# ReducedSolidWorksModel.net
KiCad netlist of a schematic drawn in EAGLE
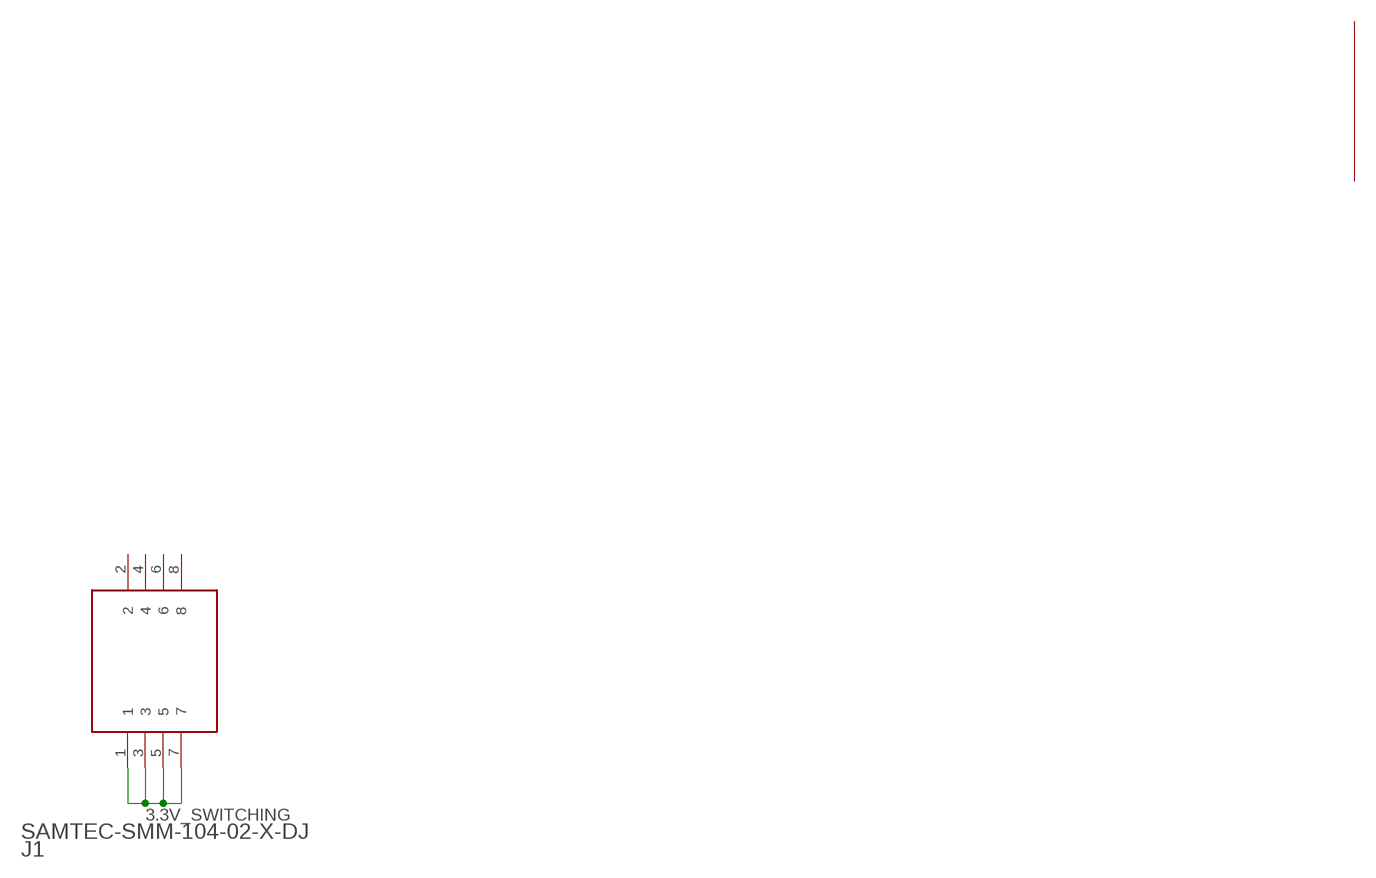
[diagram p0: schematic, sheet 3]
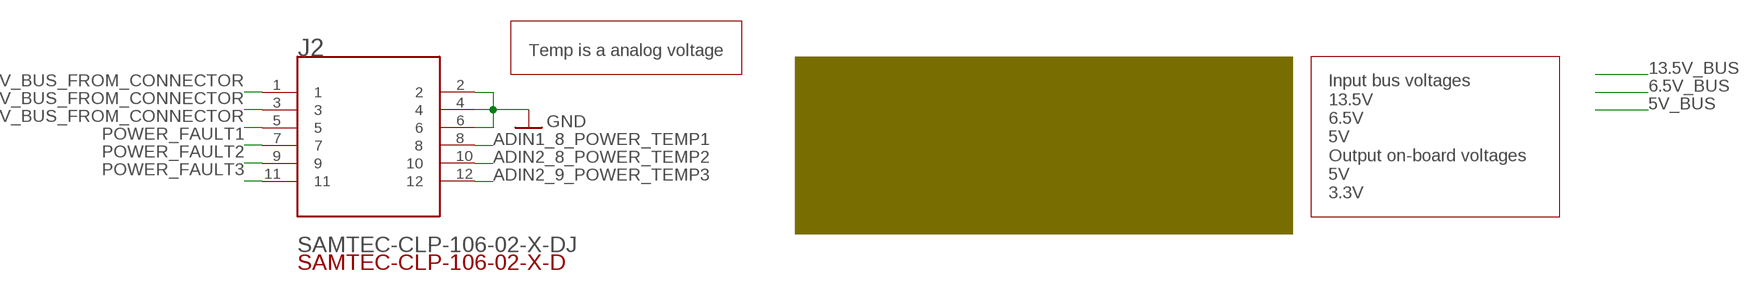
[diagram p1: schematic, sheet 4]
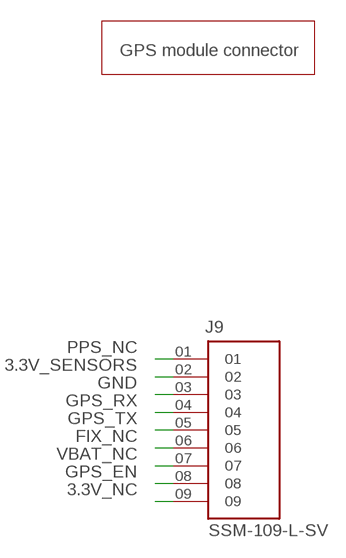
[diagram p2: schematic, sheet 7]
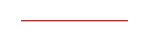
[diagram p3: schematic, sheet 10]
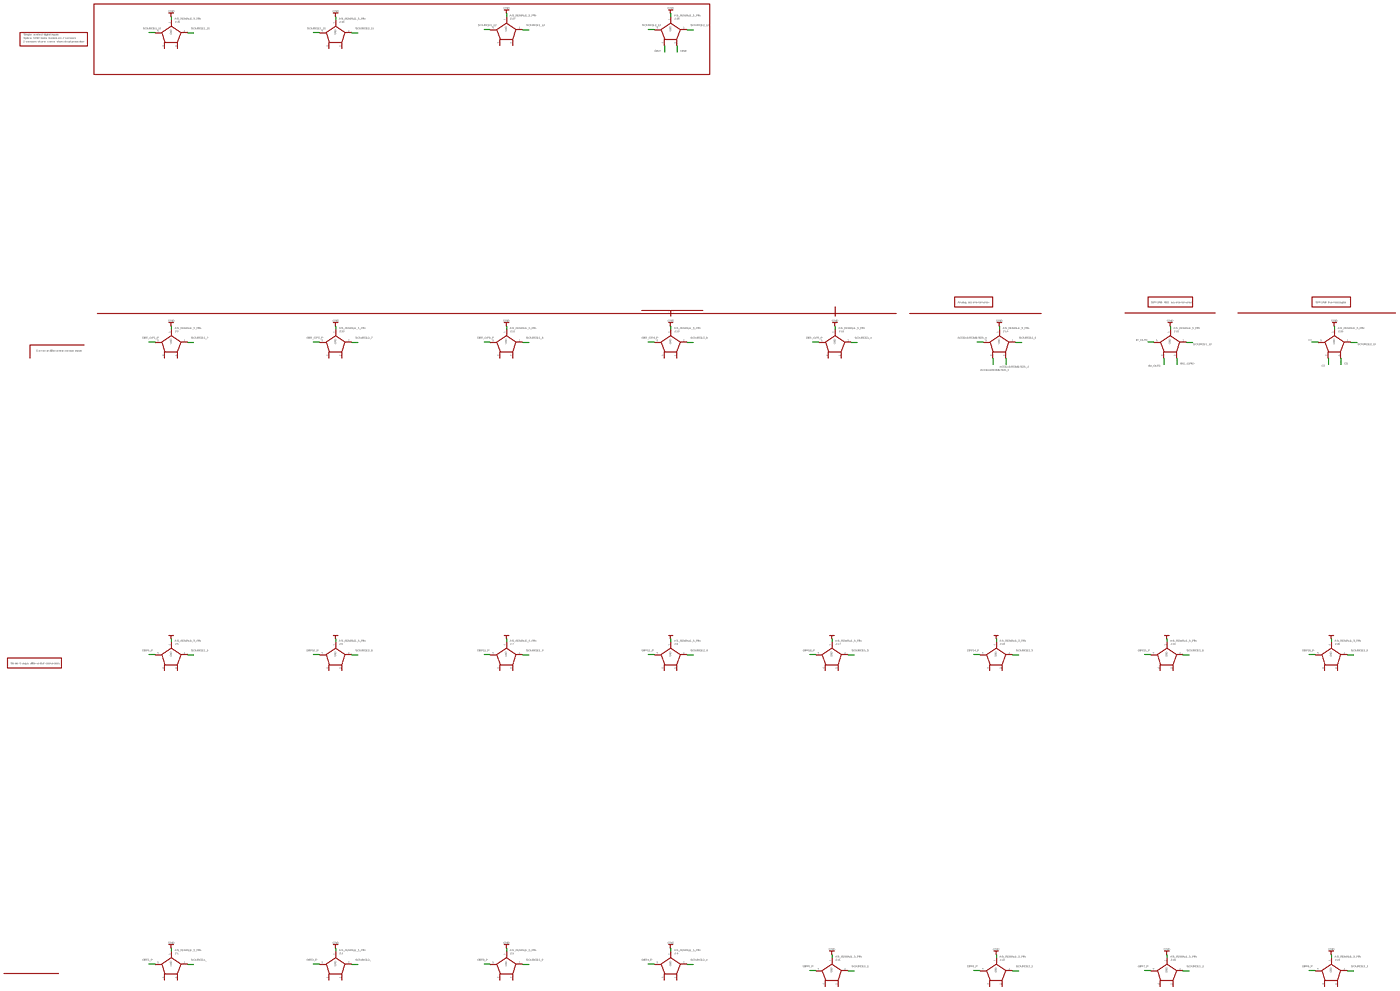
[diagram p4: schematic, sheet 11, overview]
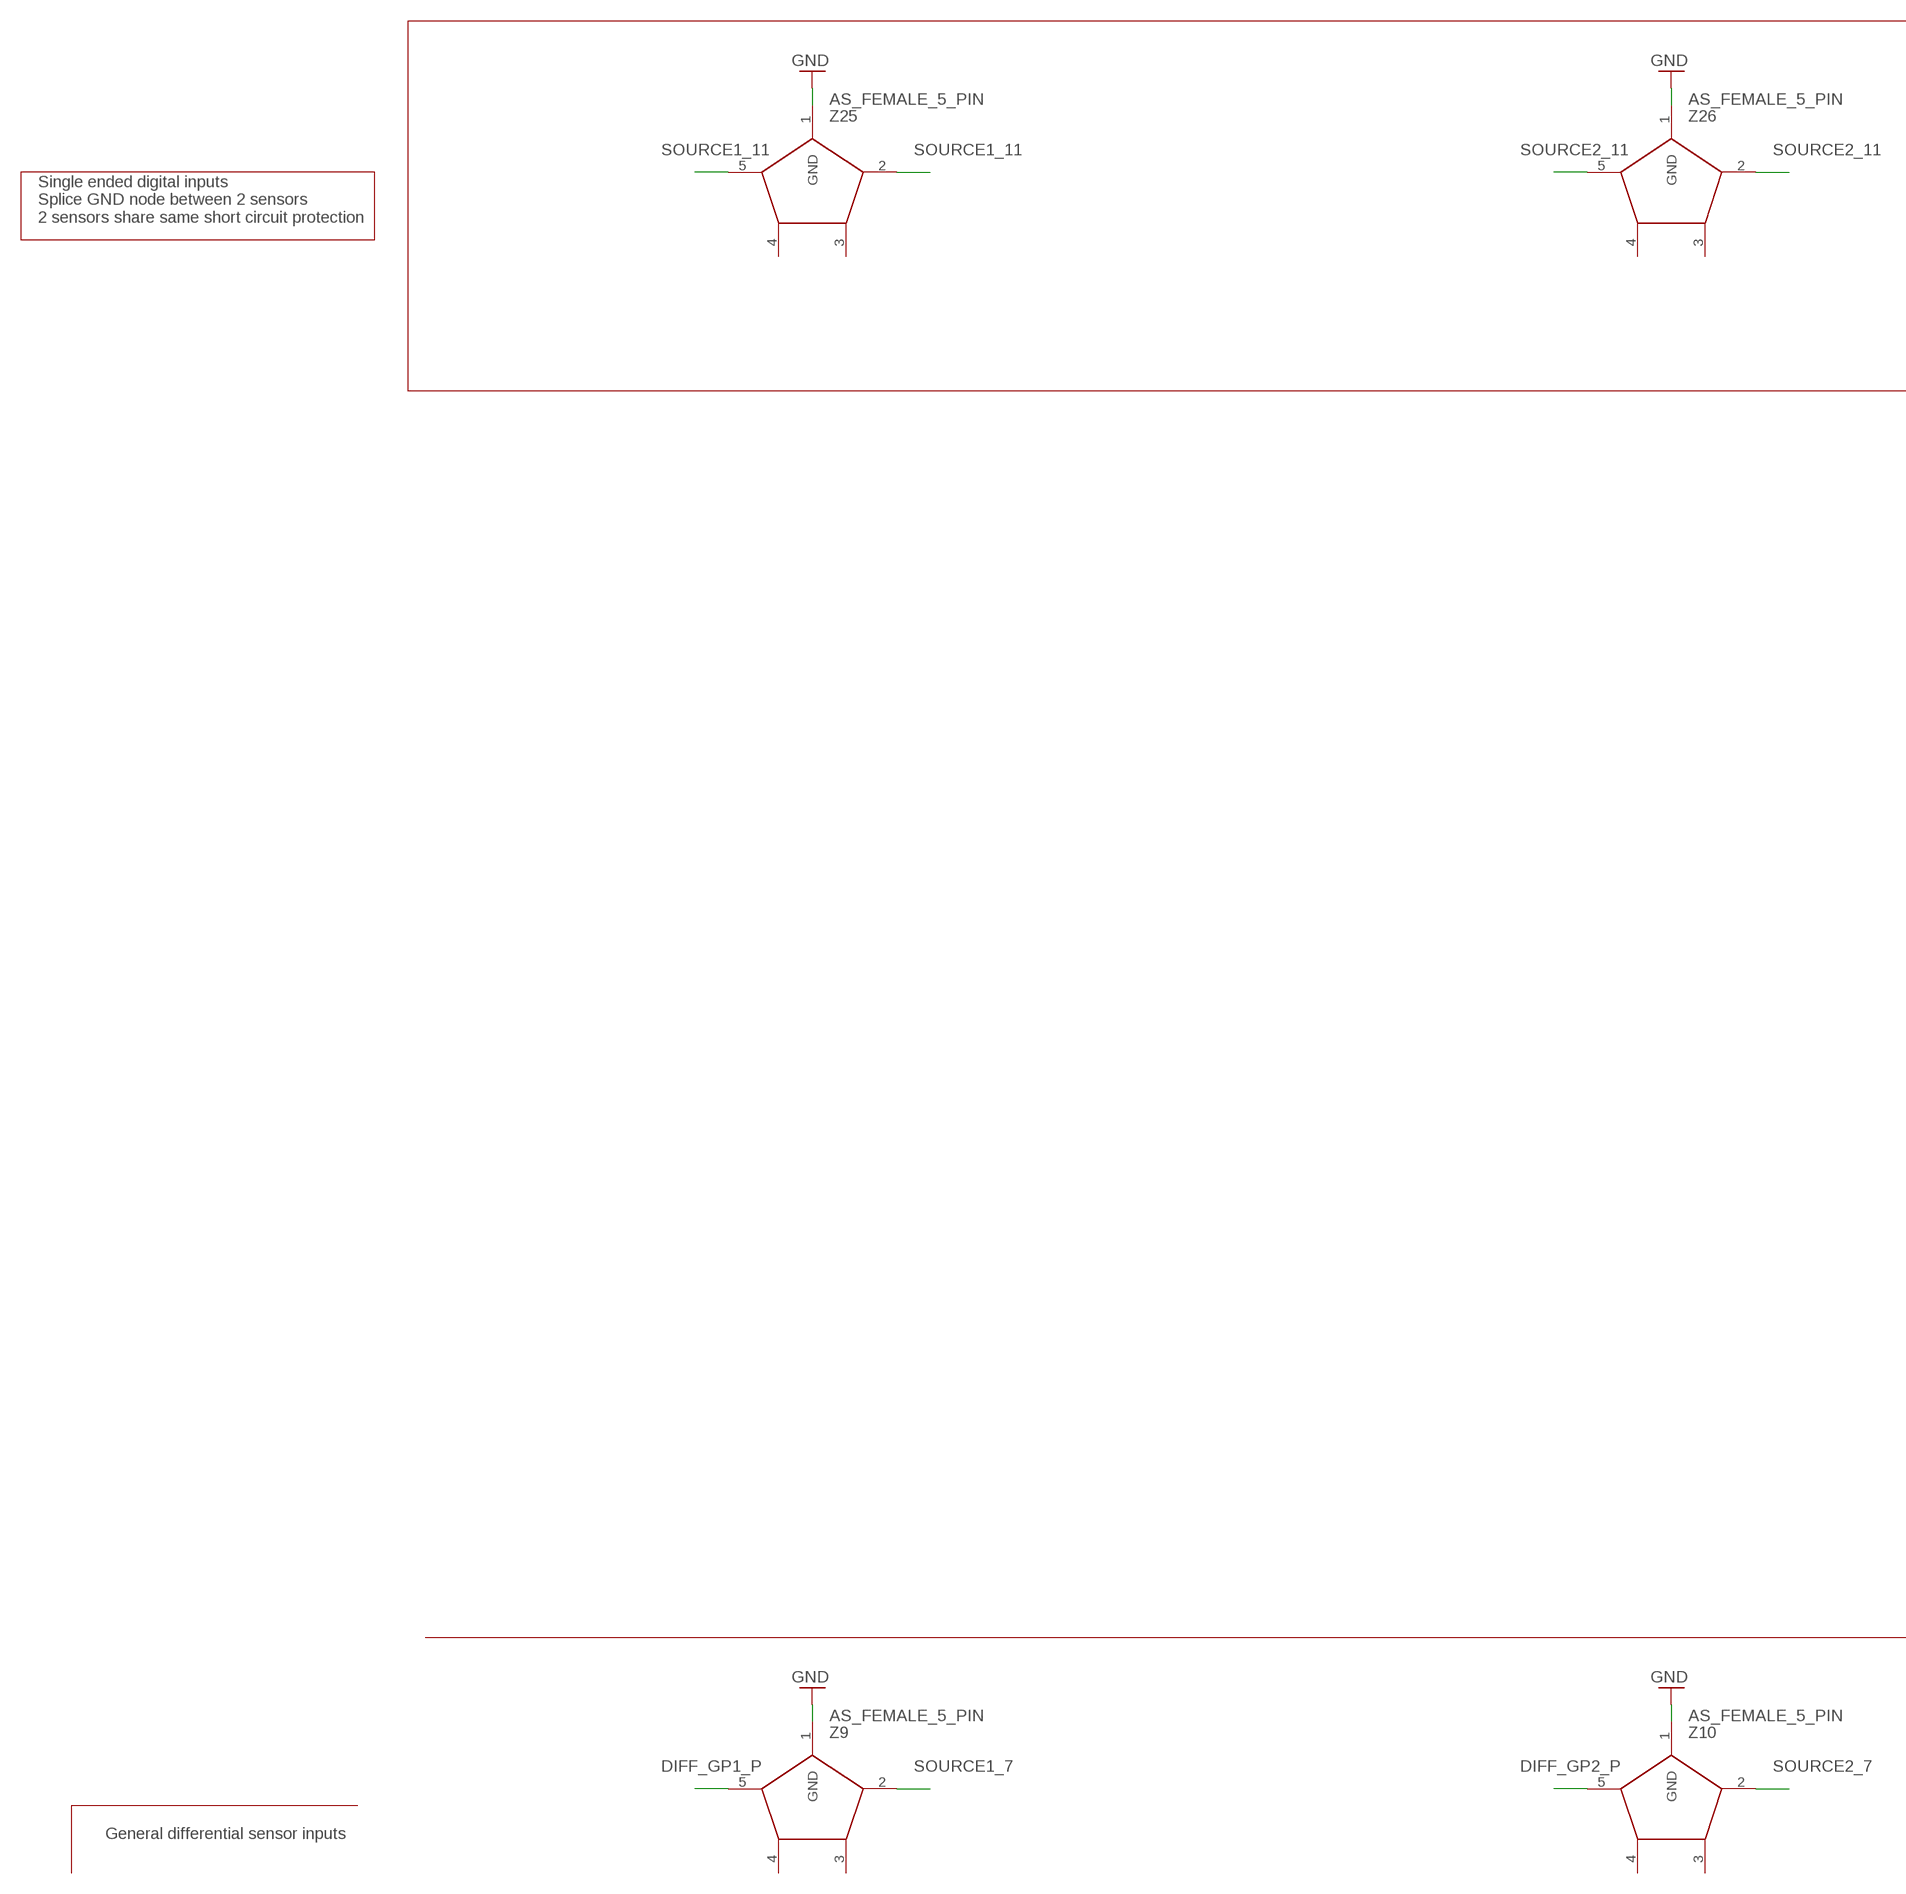
[diagram p5: schematic, sheet 11, part 1 of 7]
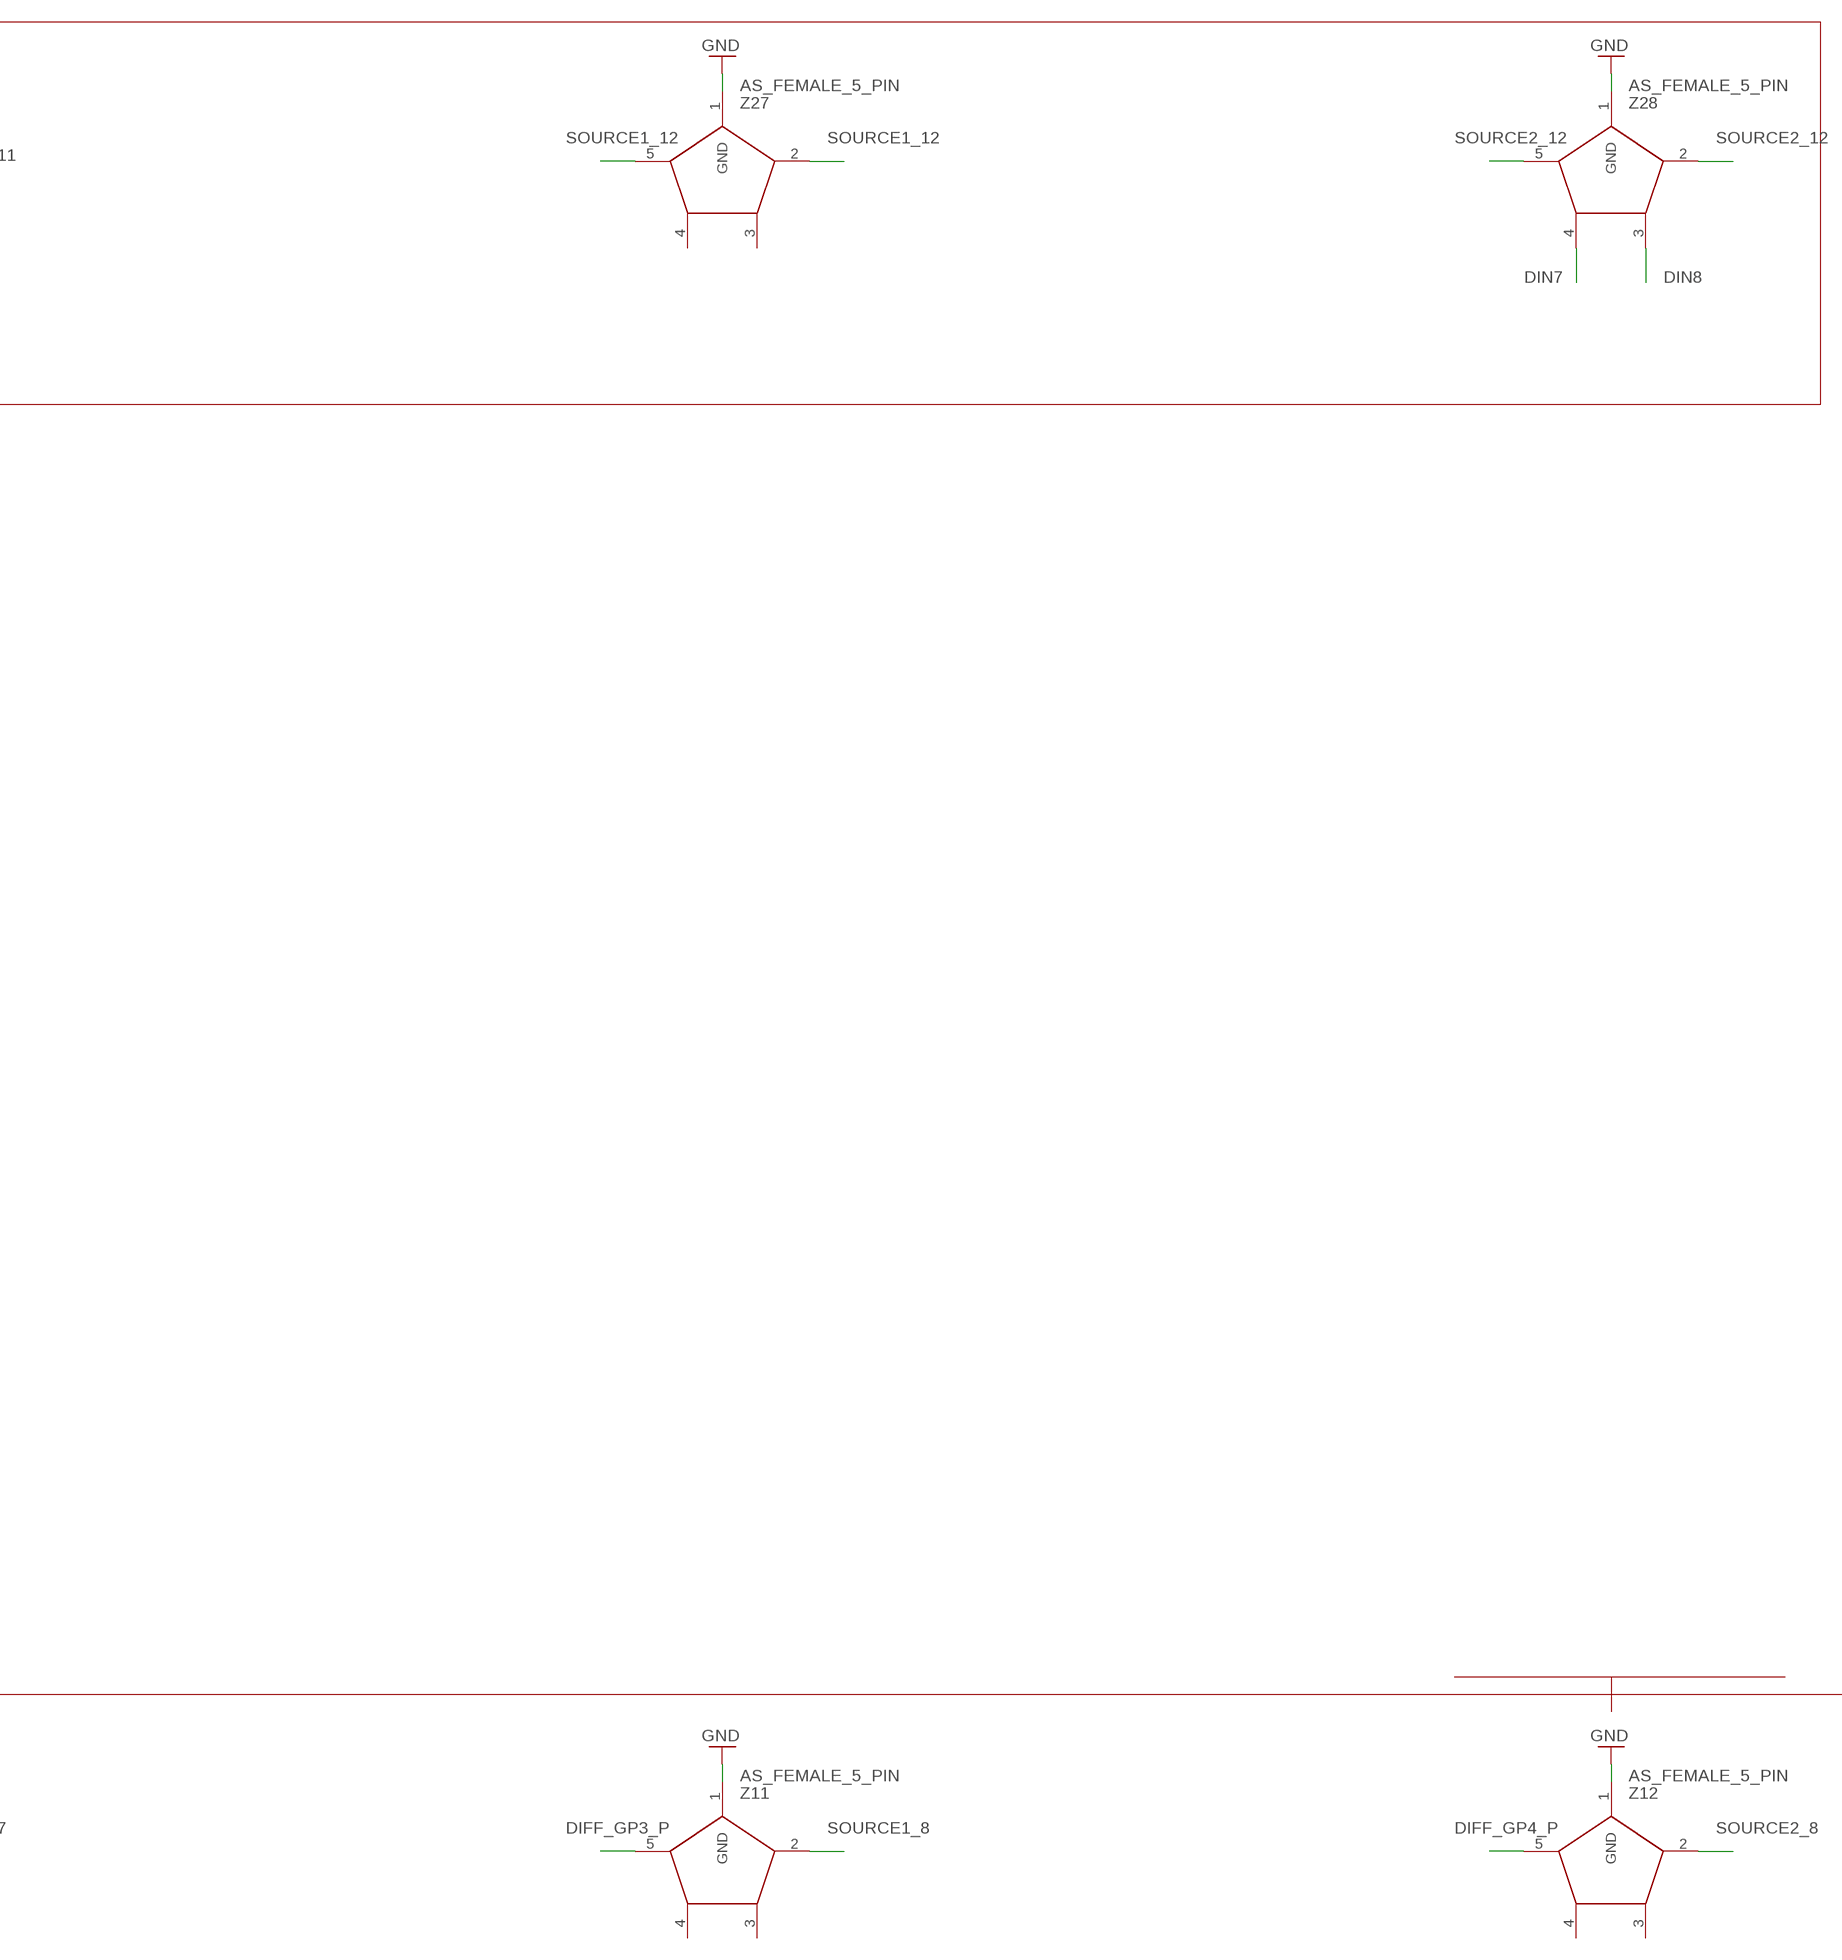
[diagram p6: schematic, sheet 11, part 2 of 7]
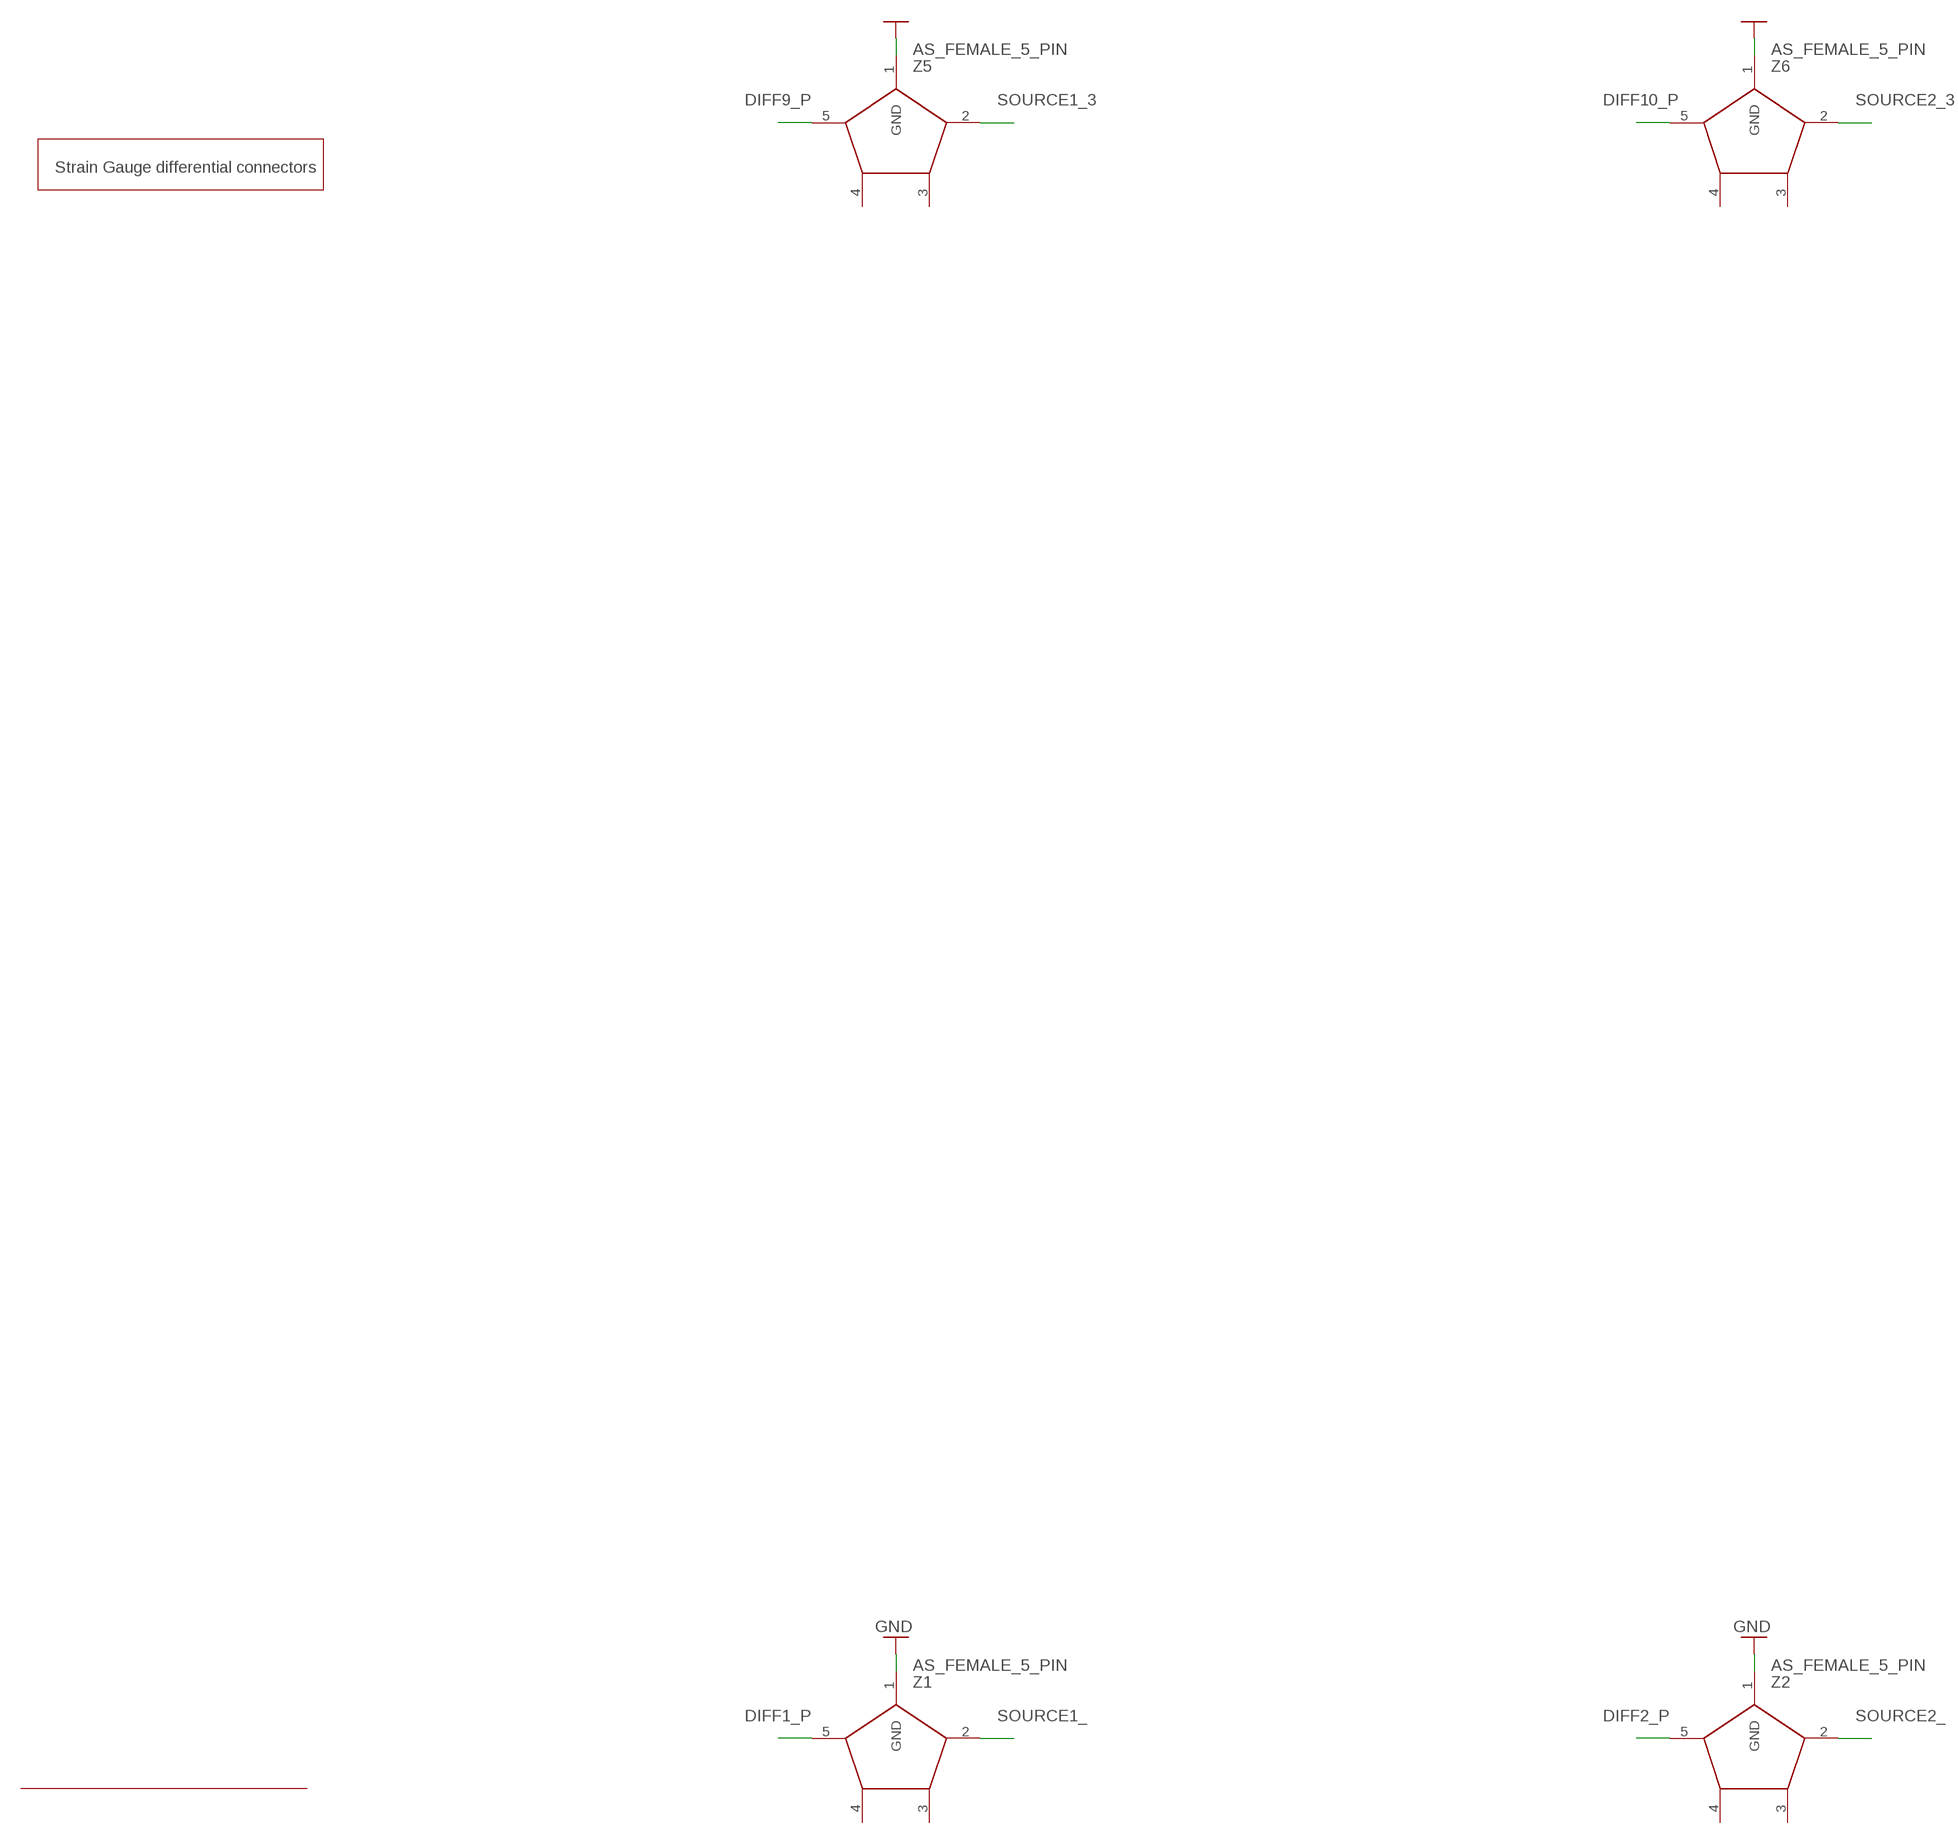
[diagram p7: schematic, sheet 11, part 3 of 7]
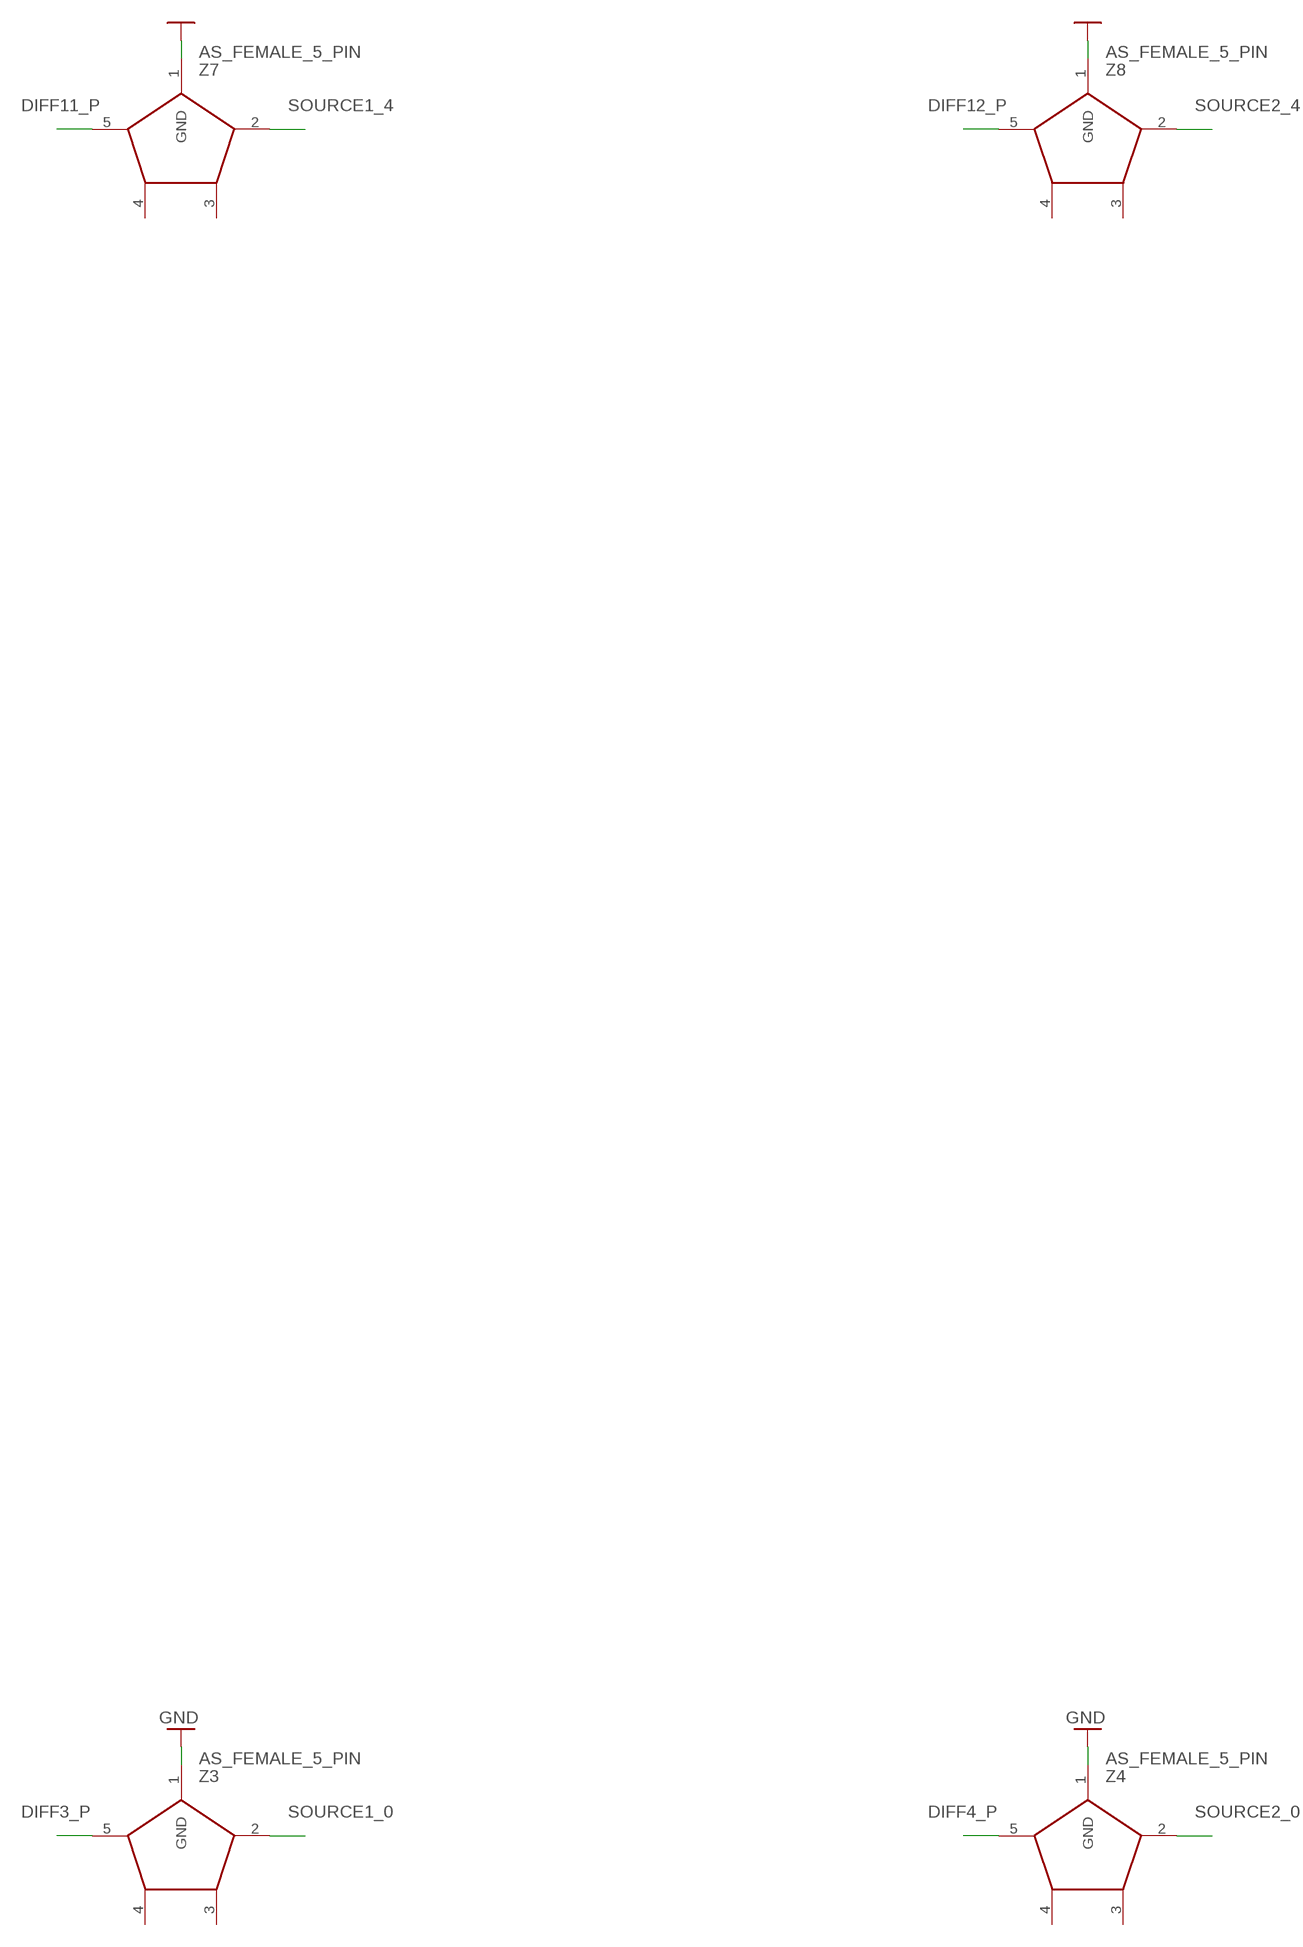
[diagram p8: schematic, sheet 11, part 4 of 7]
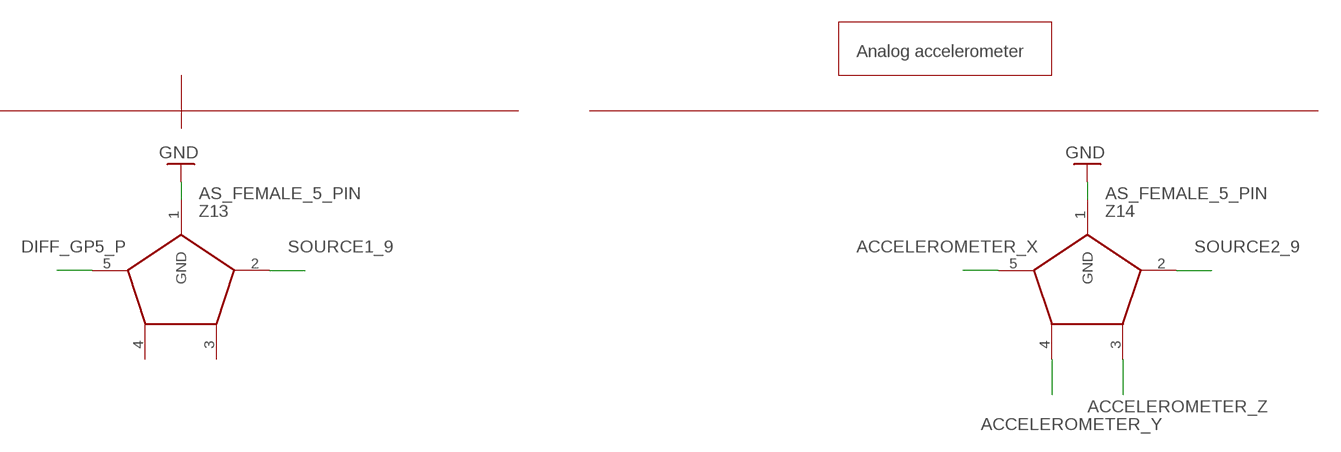
[diagram p9: schematic, sheet 11, part 5 of 7]
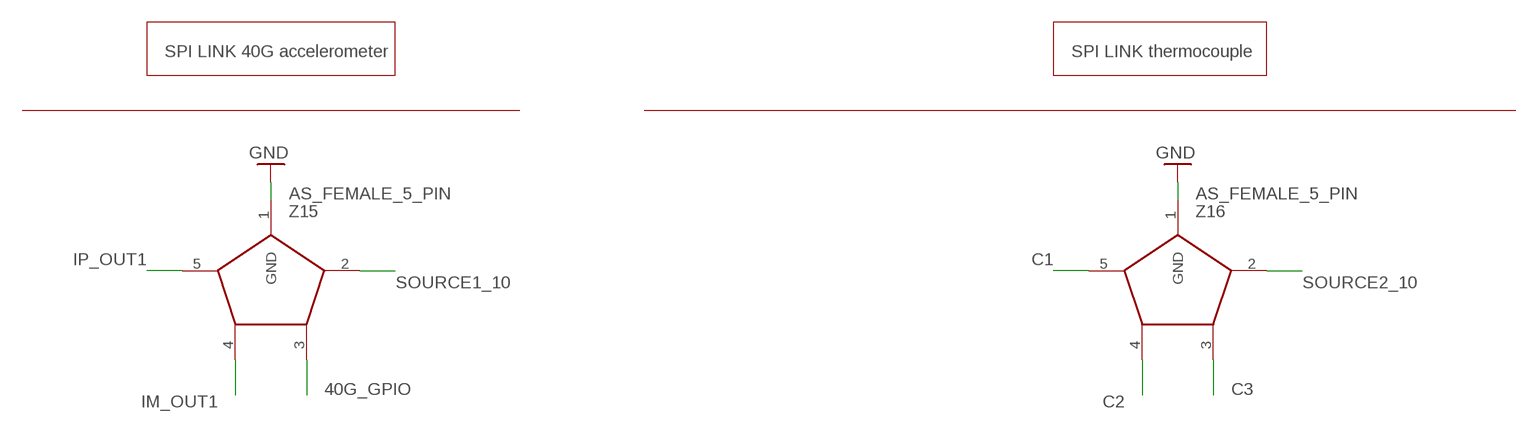
[diagram p10: schematic, sheet 11, part 6 of 7]
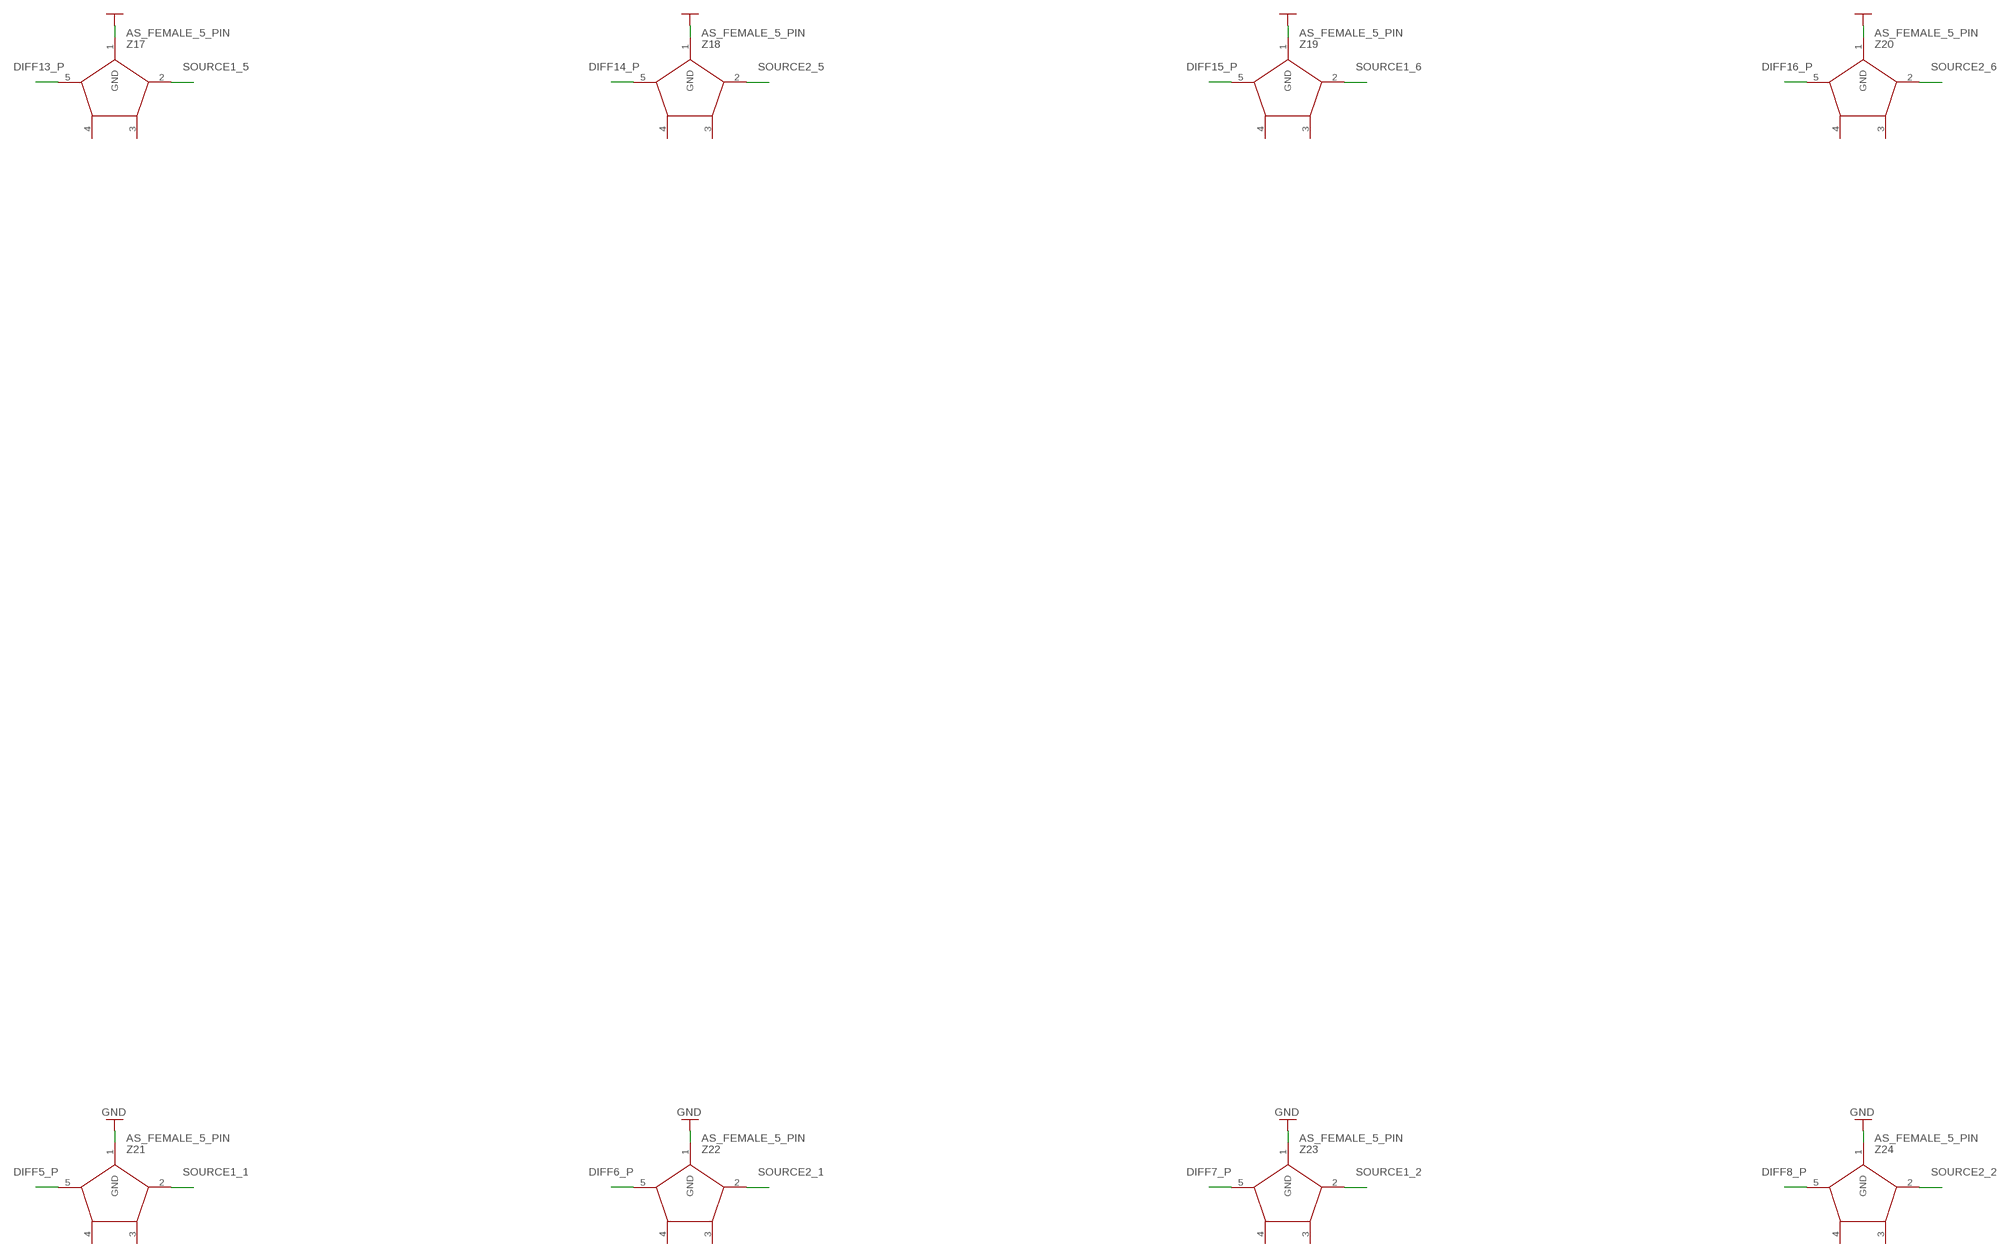
[diagram p11: schematic, sheet 11, part 7 of 7]
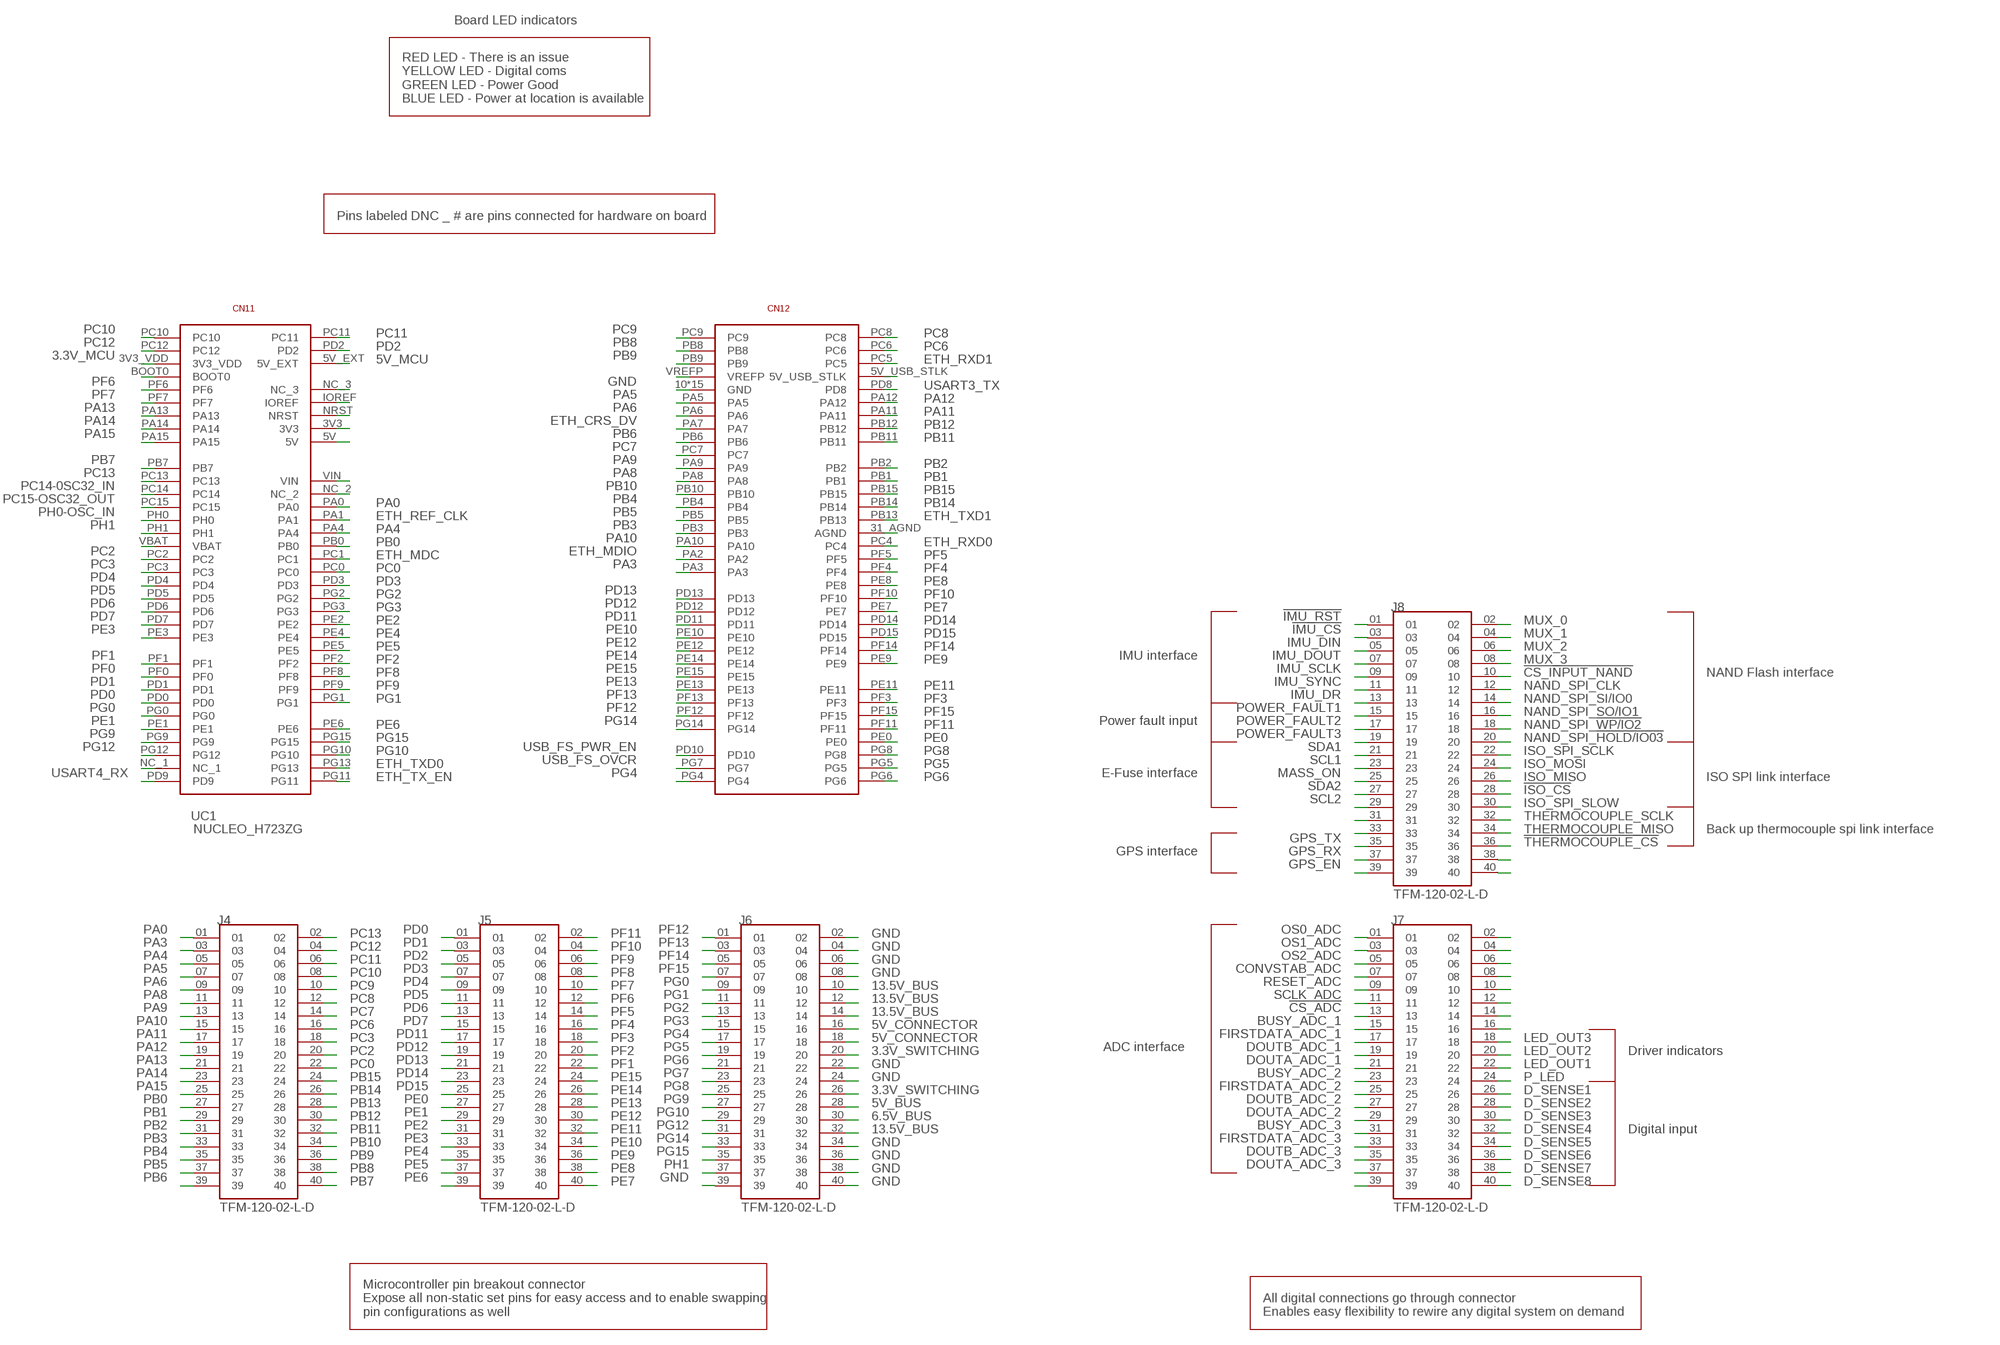
[diagram p12: schematic, sheet 12]

(export (version "E")
  (design (tool "Eeschema 10.0.6"))
  (components
    (comp (ref "J2")
      (value "SAMTEC-CLP-106-02-X-DJ")
      (footprint "eagle-import:SAMTEC-CLP-106-02-X-D")
      (libsource (lib "eagle-import") (part "SAMTEC-CLP-106-02-X-DJ"))
    )
    (comp (ref "Z1")
      (value "AS_FEMALE_5_PIN")
      (footprint "eagle-import:AS_FEMALE_5_PIN")
      (libsource (lib "eagle-import") (part "AS_FEMALE_5_PIN"))
    )
    (comp (ref "Z2")
      (value "AS_FEMALE_5_PIN")
      (footprint "eagle-import:AS_FEMALE_5_PIN")
      (libsource (lib "eagle-import") (part "AS_FEMALE_5_PIN"))
    )
    (comp (ref "Z3")
      (value "AS_FEMALE_5_PIN")
      (footprint "eagle-import:AS_FEMALE_5_PIN")
      (libsource (lib "eagle-import") (part "AS_FEMALE_5_PIN"))
    )
    (comp (ref "Z4")
      (value "AS_FEMALE_5_PIN")
      (footprint "eagle-import:AS_FEMALE_5_PIN")
      (libsource (lib "eagle-import") (part "AS_FEMALE_5_PIN"))
    )
    (comp (ref "Z5")
      (value "AS_FEMALE_5_PIN")
      (footprint "eagle-import:AS_FEMALE_5_PIN")
      (libsource (lib "eagle-import") (part "AS_FEMALE_5_PIN"))
    )
    (comp (ref "Z6")
      (value "AS_FEMALE_5_PIN")
      (footprint "eagle-import:AS_FEMALE_5_PIN")
      (libsource (lib "eagle-import") (part "AS_FEMALE_5_PIN"))
    )
    (comp (ref "Z7")
      (value "AS_FEMALE_5_PIN")
      (footprint "eagle-import:AS_FEMALE_5_PIN")
      (libsource (lib "eagle-import") (part "AS_FEMALE_5_PIN"))
    )
    (comp (ref "Z8")
      (value "AS_FEMALE_5_PIN")
      (footprint "eagle-import:AS_FEMALE_5_PIN")
      (libsource (lib "eagle-import") (part "AS_FEMALE_5_PIN"))
    )
    (comp (ref "Z9")
      (value "AS_FEMALE_5_PIN")
      (footprint "eagle-import:AS_FEMALE_5_PIN")
      (libsource (lib "eagle-import") (part "AS_FEMALE_5_PIN"))
    )
    (comp (ref "Z10")
      (value "AS_FEMALE_5_PIN")
      (footprint "eagle-import:AS_FEMALE_5_PIN")
      (libsource (lib "eagle-import") (part "AS_FEMALE_5_PIN"))
    )
    (comp (ref "Z11")
      (value "AS_FEMALE_5_PIN")
      (footprint "eagle-import:AS_FEMALE_5_PIN")
      (libsource (lib "eagle-import") (part "AS_FEMALE_5_PIN"))
    )
    (comp (ref "Z12")
      (value "AS_FEMALE_5_PIN")
      (footprint "eagle-import:AS_FEMALE_5_PIN")
      (libsource (lib "eagle-import") (part "AS_FEMALE_5_PIN"))
    )
    (comp (ref "Z13")
      (value "AS_FEMALE_5_PIN")
      (footprint "eagle-import:AS_FEMALE_5_PIN")
      (libsource (lib "eagle-import") (part "AS_FEMALE_5_PIN"))
    )
    (comp (ref "Z14")
      (value "AS_FEMALE_5_PIN")
      (footprint "eagle-import:AS_FEMALE_5_PIN")
      (libsource (lib "eagle-import") (part "AS_FEMALE_5_PIN"))
    )
    (comp (ref "Z15")
      (value "AS_FEMALE_5_PIN")
      (footprint "eagle-import:AS_FEMALE_5_PIN")
      (libsource (lib "eagle-import") (part "AS_FEMALE_5_PIN"))
    )
    (comp (ref "Z16")
      (value "AS_FEMALE_5_PIN")
      (footprint "eagle-import:AS_FEMALE_5_PIN")
      (libsource (lib "eagle-import") (part "AS_FEMALE_5_PIN"))
    )
    (comp (ref "Z17")
      (value "AS_FEMALE_5_PIN")
      (footprint "eagle-import:AS_FEMALE_5_PIN")
      (libsource (lib "eagle-import") (part "AS_FEMALE_5_PIN"))
    )
    (comp (ref "Z18")
      (value "AS_FEMALE_5_PIN")
      (footprint "eagle-import:AS_FEMALE_5_PIN")
      (libsource (lib "eagle-import") (part "AS_FEMALE_5_PIN"))
    )
    (comp (ref "Z19")
      (value "AS_FEMALE_5_PIN")
      (footprint "eagle-import:AS_FEMALE_5_PIN")
      (libsource (lib "eagle-import") (part "AS_FEMALE_5_PIN"))
    )
    (comp (ref "Z20")
      (value "AS_FEMALE_5_PIN")
      (footprint "eagle-import:AS_FEMALE_5_PIN")
      (libsource (lib "eagle-import") (part "AS_FEMALE_5_PIN"))
    )
    (comp (ref "Z21")
      (value "AS_FEMALE_5_PIN")
      (footprint "eagle-import:AS_FEMALE_5_PIN")
      (libsource (lib "eagle-import") (part "AS_FEMALE_5_PIN"))
    )
    (comp (ref "Z22")
      (value "AS_FEMALE_5_PIN")
      (footprint "eagle-import:AS_FEMALE_5_PIN")
      (libsource (lib "eagle-import") (part "AS_FEMALE_5_PIN"))
    )
    (comp (ref "Z23")
      (value "AS_FEMALE_5_PIN")
      (footprint "eagle-import:AS_FEMALE_5_PIN")
      (libsource (lib "eagle-import") (part "AS_FEMALE_5_PIN"))
    )
    (comp (ref "Z24")
      (value "AS_FEMALE_5_PIN")
      (footprint "eagle-import:AS_FEMALE_5_PIN")
      (libsource (lib "eagle-import") (part "AS_FEMALE_5_PIN"))
    )
    (comp (ref "Z25")
      (value "AS_FEMALE_5_PIN")
      (footprint "eagle-import:AS_FEMALE_5_PIN")
      (libsource (lib "eagle-import") (part "AS_FEMALE_5_PIN"))
    )
    (comp (ref "Z26")
      (value "AS_FEMALE_5_PIN")
      (footprint "eagle-import:AS_FEMALE_5_PIN")
      (libsource (lib "eagle-import") (part "AS_FEMALE_5_PIN"))
    )
    (comp (ref "Z27")
      (value "AS_FEMALE_5_PIN")
      (footprint "eagle-import:AS_FEMALE_5_PIN")
      (libsource (lib "eagle-import") (part "AS_FEMALE_5_PIN"))
    )
    (comp (ref "Z28")
      (value "AS_FEMALE_5_PIN")
      (footprint "eagle-import:AS_FEMALE_5_PIN")
      (libsource (lib "eagle-import") (part "AS_FEMALE_5_PIN"))
    )
    (comp (ref "J9")
      (value "SSM-109-L-SV")
      (footprint "eagle-import:SAMTEC_SSM-109-L-SV")
      (fields (field (name "MANUFACTURER") "SAMTEC "))
      (libsource (lib "eagle-import") (part "SSM-109-L-SV"))
    )
    (comp (ref "J1")
      (value "SAMTEC-SMM-104-02-X-DJ")
      (footprint "eagle-import:SAMTEC-SMM-104-02-X-D")
      (libsource (lib "eagle-import") (part "SAMTEC-SMM-104-02-X-DJ"))
    )
    (comp (ref "J4")
      (value "TFM-120-02-L-D")
      (footprint "eagle-import:SAMTEC_TFM-120-02-L-D")
      (fields (field (name "MANUFACTURER") "Samtec"))
      (libsource (lib "eagle-import") (part "TFM-120-02-L-D"))
    )
    (comp (ref "J5")
      (value "TFM-120-02-L-D")
      (footprint "eagle-import:SAMTEC_TFM-120-02-L-D")
      (fields (field (name "MANUFACTURER") "Samtec"))
      (libsource (lib "eagle-import") (part "TFM-120-02-L-D"))
    )
    (comp (ref "J6")
      (value "TFM-120-02-L-D")
      (footprint "eagle-import:SAMTEC_TFM-120-02-L-D")
      (fields (field (name "MANUFACTURER") "Samtec"))
      (libsource (lib "eagle-import") (part "TFM-120-02-L-D"))
    )
    (comp (ref "J7")
      (value "TFM-120-02-L-D")
      (footprint "eagle-import:SAMTEC_TFM-120-02-L-D")
      (fields (field (name "MANUFACTURER") "Samtec"))
      (libsource (lib "eagle-import") (part "TFM-120-02-L-D"))
    )
    (comp (ref "J8")
      (value "TFM-120-02-L-D")
      (footprint "eagle-import:SAMTEC_TFM-120-02-L-D")
      (fields (field (name "MANUFACTURER") "Samtec"))
      (libsource (lib "eagle-import") (part "TFM-120-02-L-D"))
    )
    (comp (ref "UC1")
      (value "NUCLEO_H723ZG")
      (footprint "eagle-import:NUCLEO_H723ZG")
      (libsource (lib "eagle-import") (part "NUCLEO_H723ZG"))
    )
  )
  (nets
    (net (code "1") (name "3.3V_MCU") (class "Default")
      (node (ref "UC1") (pin "3V3_VDD") (pinfunction "3V3_VDD_3V3_VDD") (pintype "passive"))
    )
    (net (code "2") (name "3.3V_NC") (class "Default")
      (node (ref "J9") (pin "09") (pinfunction "09_09") (pintype "passive"))
    )
    (net (code "3") (name "3.3V_SENSORS") (class "Default")
      (node (ref "J9") (pin "02") (pinfunction "02_02") (pintype "passive"))
    )
    (net (code "4") (name "3.3V_SWITCHING") (class "Default")
      (node (ref "J1") (pin "1") (pinfunction "1_1") (pintype "passive"))
      (node (ref "J1") (pin "3") (pinfunction "3_3") (pintype "passive"))
      (node (ref "J1") (pin "5") (pinfunction "5_5") (pintype "passive"))
      (node (ref "J1") (pin "7") (pinfunction "7_7") (pintype "passive"))
      (node (ref "J6") (pin "20") (pinfunction "20_20") (pintype "passive"))
      (node (ref "J6") (pin "26") (pinfunction "26_26") (pintype "passive"))
    )
    (net (code "5") (name "5V_BUS") (class "Default")
      (node (ref "J6") (pin "28") (pinfunction "28_28") (pintype "passive"))
    )
    (net (code "6") (name "5V_BUS_FROM_CONNECTOR") (class "Default")
      (node (ref "J2") (pin "5") (pinfunction "5_5") (pintype "passive"))
    )
    (net (code "7") (name "5V_CONNECTOR") (class "Default")
      (node (ref "J6") (pin "16") (pinfunction "16_16") (pintype "passive"))
      (node (ref "J6") (pin "18") (pinfunction "18_18") (pintype "passive"))
    )
    (net (code "8") (name "5V_MCU") (class "Default")
      (node (ref "UC1") (pin "5V_EXT") (pinfunction "5V_EXT_5V_EXT") (pintype "passive"))
    )
    (net (code "9") (name "6.5V_BUS") (class "Default")
      (node (ref "J6") (pin "30") (pinfunction "30_30") (pintype "passive"))
    )
    (net (code "10") (name "6.5V_BUS_FROM_CONNECTOR") (class "Default")
      (node (ref "J2") (pin "3") (pinfunction "3_3") (pintype "passive"))
    )
    (net (code "11") (name "13.5V_BUS") (class "Default")
      (node (ref "J6") (pin "10") (pinfunction "10_10") (pintype "passive"))
      (node (ref "J6") (pin "12") (pinfunction "12_12") (pintype "passive"))
      (node (ref "J6") (pin "14") (pinfunction "14_14") (pintype "passive"))
      (node (ref "J6") (pin "32") (pinfunction "32_32") (pintype "passive"))
    )
    (net (code "12") (name "14V_BUS_FROM_CONNECTOR") (class "Default")
      (node (ref "J2") (pin "1") (pinfunction "1_1") (pintype "passive"))
    )
    (net (code "13") (name "40G_GPIO") (class "Default")
      (node (ref "Z15") (pin "3") (pinfunction "2_3") (pintype "bidirectional"))
    )
    (net (code "14") (name "ACCELEROMETER_X") (class "Default")
      (node (ref "Z14") (pin "5") (pinfunction "4_5") (pintype "bidirectional"))
    )
    (net (code "15") (name "ACCELEROMETER_Y") (class "Default")
      (node (ref "Z14") (pin "4") (pinfunction "3_4") (pintype "bidirectional"))
    )
    (net (code "16") (name "ACCELEROMETER_Z") (class "Default")
      (node (ref "Z14") (pin "3") (pinfunction "2_3") (pintype "bidirectional"))
    )
    (net (code "17") (name "ADIN1_8_POWER_TEMP1") (class "Default")
      (node (ref "J2") (pin "8") (pinfunction "8_8") (pintype "passive"))
    )
    (net (code "18") (name "ADIN2_8_POWER_TEMP2") (class "Default")
      (node (ref "J2") (pin "10") (pinfunction "10_10") (pintype "passive"))
    )
    (net (code "19") (name "ADIN2_9_POWER_TEMP3") (class "Default")
      (node (ref "J2") (pin "12") (pinfunction "12_12") (pintype "passive"))
    )
    (net (code "20") (name "BUSY_ADC_1") (class "Default")
      (node (ref "J7") (pin "15") (pinfunction "15_15") (pintype "passive"))
    )
    (net (code "21") (name "BUSY_ADC_2") (class "Default")
      (node (ref "J7") (pin "23") (pinfunction "23_23") (pintype "passive"))
    )
    (net (code "22") (name "BUSY_ADC_3") (class "Default")
      (node (ref "J7") (pin "31") (pinfunction "31_31") (pintype "passive"))
    )
    (net (code "23") (name "C1") (class "Default")
      (node (ref "Z16") (pin "5") (pinfunction "4_5") (pintype "bidirectional"))
    )
    (net (code "24") (name "C2") (class "Default")
      (node (ref "Z16") (pin "4") (pinfunction "3_4") (pintype "bidirectional"))
    )
    (net (code "25") (name "C3") (class "Default")
      (node (ref "Z16") (pin "3") (pinfunction "2_3") (pintype "bidirectional"))
    )
    (net (code "26") (name "CONVSTAB_ADC") (class "Default")
      (node (ref "J7") (pin "07") (pinfunction "07_07") (pintype "passive"))
    )
    (net (code "27") (name "DIFF1_P") (class "Default")
      (node (ref "Z1") (pin "5") (pinfunction "4_5") (pintype "bidirectional"))
    )
    (net (code "28") (name "DIFF2_P") (class "Default")
      (node (ref "Z2") (pin "5") (pinfunction "4_5") (pintype "bidirectional"))
    )
    (net (code "29") (name "DIFF3_P") (class "Default")
      (node (ref "Z3") (pin "5") (pinfunction "4_5") (pintype "bidirectional"))
    )
    (net (code "30") (name "DIFF4_P") (class "Default")
      (node (ref "Z4") (pin "5") (pinfunction "4_5") (pintype "bidirectional"))
    )
    (net (code "31") (name "DIFF5_P") (class "Default")
      (node (ref "Z21") (pin "5") (pinfunction "4_5") (pintype "bidirectional"))
    )
    (net (code "32") (name "DIFF6_P") (class "Default")
      (node (ref "Z22") (pin "5") (pinfunction "4_5") (pintype "bidirectional"))
    )
    (net (code "33") (name "DIFF7_P") (class "Default")
      (node (ref "Z23") (pin "5") (pinfunction "4_5") (pintype "bidirectional"))
    )
    (net (code "34") (name "DIFF8_P") (class "Default")
      (node (ref "Z24") (pin "5") (pinfunction "4_5") (pintype "bidirectional"))
    )
    (net (code "35") (name "DIFF9_P") (class "Default")
      (node (ref "Z5") (pin "5") (pinfunction "4_5") (pintype "bidirectional"))
    )
    (net (code "36") (name "DIFF10_P") (class "Default")
      (node (ref "Z6") (pin "5") (pinfunction "4_5") (pintype "bidirectional"))
    )
    (net (code "37") (name "DIFF11_P") (class "Default")
      (node (ref "Z7") (pin "5") (pinfunction "4_5") (pintype "bidirectional"))
    )
    (net (code "38") (name "DIFF12_P") (class "Default")
      (node (ref "Z8") (pin "5") (pinfunction "4_5") (pintype "bidirectional"))
    )
    (net (code "39") (name "DIFF13_P") (class "Default")
      (node (ref "Z17") (pin "5") (pinfunction "4_5") (pintype "bidirectional"))
    )
    (net (code "40") (name "DIFF14_P") (class "Default")
      (node (ref "Z18") (pin "5") (pinfunction "4_5") (pintype "bidirectional"))
    )
    (net (code "41") (name "DIFF15_P") (class "Default")
      (node (ref "Z19") (pin "5") (pinfunction "4_5") (pintype "bidirectional"))
    )
    (net (code "42") (name "DIFF16_P") (class "Default")
      (node (ref "Z20") (pin "5") (pinfunction "4_5") (pintype "bidirectional"))
    )
    (net (code "43") (name "DIFF_GP1_P") (class "Default")
      (node (ref "Z9") (pin "5") (pinfunction "4_5") (pintype "bidirectional"))
    )
    (net (code "44") (name "DIFF_GP2_P") (class "Default")
      (node (ref "Z10") (pin "5") (pinfunction "4_5") (pintype "bidirectional"))
    )
    (net (code "45") (name "DIFF_GP3_P") (class "Default")
      (node (ref "Z11") (pin "5") (pinfunction "4_5") (pintype "bidirectional"))
    )
    (net (code "46") (name "DIFF_GP4_P") (class "Default")
      (node (ref "Z12") (pin "5") (pinfunction "4_5") (pintype "bidirectional"))
    )
    (net (code "47") (name "DIFF_GP5_P") (class "Default")
      (node (ref "Z13") (pin "5") (pinfunction "4_5") (pintype "bidirectional"))
    )
    (net (code "48") (name "DIN7") (class "Default")
      (node (ref "Z28") (pin "4") (pinfunction "3_4") (pintype "bidirectional"))
    )
    (net (code "49") (name "DIN8") (class "Default")
      (node (ref "Z28") (pin "3") (pinfunction "2_3") (pintype "bidirectional"))
    )
    (net (code "50") (name "DOUTA_ADC_1") (class "Default")
      (node (ref "J7") (pin "21") (pinfunction "21_21") (pintype "passive"))
    )
    (net (code "51") (name "DOUTA_ADC_2") (class "Default")
      (node (ref "J7") (pin "29") (pinfunction "29_29") (pintype "passive"))
    )
    (net (code "52") (name "DOUTA_ADC_3") (class "Default")
      (node (ref "J7") (pin "37") (pinfunction "37_37") (pintype "passive"))
    )
    (net (code "53") (name "DOUTB_ADC_1") (class "Default")
      (node (ref "J7") (pin "19") (pinfunction "19_19") (pintype "passive"))
    )
    (net (code "54") (name "DOUTB_ADC_2") (class "Default")
      (node (ref "J7") (pin "27") (pinfunction "27_27") (pintype "passive"))
    )
    (net (code "55") (name "DOUTB_ADC_3") (class "Default")
      (node (ref "J7") (pin "35") (pinfunction "35_35") (pintype "passive"))
    )
    (net (code "56") (name "D_SENSE1") (class "Default")
      (node (ref "J7") (pin "26") (pinfunction "26_26") (pintype "passive"))
    )
    (net (code "57") (name "D_SENSE2") (class "Default")
      (node (ref "J7") (pin "28") (pinfunction "28_28") (pintype "passive"))
    )
    (net (code "58") (name "D_SENSE3") (class "Default")
      (node (ref "J7") (pin "30") (pinfunction "30_30") (pintype "passive"))
    )
    (net (code "59") (name "D_SENSE4") (class "Default")
      (node (ref "J7") (pin "32") (pinfunction "32_32") (pintype "passive"))
    )
    (net (code "60") (name "D_SENSE5") (class "Default")
      (node (ref "J7") (pin "34") (pinfunction "34_34") (pintype "passive"))
    )
    (net (code "61") (name "D_SENSE6") (class "Default")
      (node (ref "J7") (pin "36") (pinfunction "36_36") (pintype "passive"))
    )
    (net (code "62") (name "D_SENSE7") (class "Default")
      (node (ref "J7") (pin "38") (pinfunction "38_38") (pintype "passive"))
    )
    (net (code "63") (name "D_SENSE8") (class "Default")
      (node (ref "J7") (pin "40") (pinfunction "40_40") (pintype "passive"))
    )
    (net (code "64") (name "ETH_CRS_DV") (class "Default")
      (node (ref "UC1") (pin "PA7") (pinfunction "PA7_PA7") (pintype "passive"))
    )
    (net (code "65") (name "ETH_MDC") (class "Default")
      (node (ref "UC1") (pin "PC1") (pinfunction "PC1_PC1") (pintype "passive"))
    )
    (net (code "66") (name "ETH_MDIO") (class "Default")
      (node (ref "UC1") (pin "PA2") (pinfunction "PA2_PA2") (pintype "passive"))
    )
    (net (code "67") (name "ETH_REF_CLK") (class "Default")
      (node (ref "UC1") (pin "PA1") (pinfunction "PA1_PA1") (pintype "passive"))
    )
    (net (code "68") (name "ETH_RXD0") (class "Default")
      (node (ref "UC1") (pin "PC4") (pinfunction "PC4_PC4") (pintype "passive"))
    )
    (net (code "69") (name "ETH_RXD1") (class "Default")
      (node (ref "UC1") (pin "PC5") (pinfunction "PC5_PC5") (pintype "passive"))
    )
    (net (code "70") (name "ETH_TXD0") (class "Default")
      (node (ref "UC1") (pin "PG13") (pinfunction "PG13_PG13") (pintype "passive"))
    )
    (net (code "71") (name "ETH_TXD1") (class "Default")
      (node (ref "UC1") (pin "PB13") (pinfunction "PB13_PB13") (pintype "passive"))
    )
    (net (code "72") (name "ETH_TX_EN") (class "Default")
      (node (ref "UC1") (pin "PG11") (pinfunction "PG11_PG11") (pintype "passive"))
    )
    (net (code "73") (name "FIRSTDATA_ADC_1") (class "Default")
      (node (ref "J7") (pin "17") (pinfunction "17_17") (pintype "passive"))
    )
    (net (code "74") (name "FIRSTDATA_ADC_2") (class "Default")
      (node (ref "J7") (pin "25") (pinfunction "25_25") (pintype "passive"))
    )
    (net (code "75") (name "FIRSTDATA_ADC_3") (class "Default")
      (node (ref "J7") (pin "33") (pinfunction "33_33") (pintype "passive"))
    )
    (net (code "76") (name "FIX_NC") (class "Default")
      (node (ref "J9") (pin "06") (pinfunction "06_06") (pintype "passive"))
    )
    (net (code "77") (name "GND") (class "Default")
      (node (ref "J2") (pin "2") (pinfunction "2_2") (pintype "passive"))
      (node (ref "J2") (pin "4") (pinfunction "4_4") (pintype "passive"))
      (node (ref "J2") (pin "6") (pinfunction "6_6") (pintype "passive"))
      (node (ref "J6") (pin "02") (pinfunction "02_02") (pintype "passive"))
      (node (ref "J6") (pin "04") (pinfunction "04_04") (pintype "passive"))
      (node (ref "J6") (pin "06") (pinfunction "06_06") (pintype "passive"))
      (node (ref "J6") (pin "08") (pinfunction "08_08") (pintype "passive"))
      (node (ref "J6") (pin "22") (pinfunction "22_22") (pintype "passive"))
      (node (ref "J6") (pin "24") (pinfunction "24_24") (pintype "passive"))
      (node (ref "J6") (pin "34") (pinfunction "34_34") (pintype "passive"))
      (node (ref "J6") (pin "36") (pinfunction "36_36") (pintype "passive"))
      (node (ref "J6") (pin "38") (pinfunction "38_38") (pintype "passive"))
      (node (ref "J6") (pin "39") (pinfunction "39_39") (pintype "passive"))
      (node (ref "J6") (pin "40") (pinfunction "40_40") (pintype "passive"))
      (node (ref "J9") (pin "03") (pinfunction "03_03") (pintype "passive"))
      (node (ref "UC1") (pin "10") (pinfunction "GND_10") (pintype "passive"))
      (node (ref "UC1") (pin "122") (pinfunction "GND_122") (pintype "passive"))
      (node (ref "UC1") (pin "131") (pinfunction "GND_131") (pintype "passive"))
      (node (ref "UC1") (pin "143") (pinfunction "GND_143") (pintype "passive"))
      (node (ref "UC1") (pin "144") (pinfunction "GND_144") (pintype "passive"))
      (node (ref "UC1") (pin "19") (pinfunction "GND_19") (pintype "passive"))
      (node (ref "UC1") (pin "40") (pinfunction "GND_40") (pintype "passive"))
      (node (ref "UC1") (pin "53") (pinfunction "GND_53") (pintype "passive"))
      (node (ref "UC1") (pin "64") (pinfunction "GND_64") (pintype "passive"))
      (node (ref "UC1") (pin "71") (pinfunction "GND_71") (pintype "passive"))
      (node (ref "UC1") (pin "72") (pinfunction "GND_72") (pintype "passive"))
      (node (ref "UC1") (pin "79") (pinfunction "GND_79") (pintype "passive"))
      (node (ref "UC1") (pin "91") (pinfunction "GND_91") (pintype "passive"))
      (node (ref "UC1") (pin "92") (pinfunction "GND_92") (pintype "passive"))
      (node (ref "UC1") (pin "93") (pinfunction "GND_93") (pintype "passive"))
      (node (ref "Z1") (pin "1") (pinfunction "GND_1") (pintype "bidirectional"))
      (node (ref "Z10") (pin "1") (pinfunction "GND_1") (pintype "bidirectional"))
      (node (ref "Z11") (pin "1") (pinfunction "GND_1") (pintype "bidirectional"))
      (node (ref "Z12") (pin "1") (pinfunction "GND_1") (pintype "bidirectional"))
      (node (ref "Z13") (pin "1") (pinfunction "GND_1") (pintype "bidirectional"))
      (node (ref "Z14") (pin "1") (pinfunction "GND_1") (pintype "bidirectional"))
      (node (ref "Z15") (pin "1") (pinfunction "GND_1") (pintype "bidirectional"))
      (node (ref "Z16") (pin "1") (pinfunction "GND_1") (pintype "bidirectional"))
      (node (ref "Z17") (pin "1") (pinfunction "GND_1") (pintype "bidirectional"))
      (node (ref "Z18") (pin "1") (pinfunction "GND_1") (pintype "bidirectional"))
      (node (ref "Z19") (pin "1") (pinfunction "GND_1") (pintype "bidirectional"))
      (node (ref "Z2") (pin "1") (pinfunction "GND_1") (pintype "bidirectional"))
      (node (ref "Z20") (pin "1") (pinfunction "GND_1") (pintype "bidirectional"))
      (node (ref "Z21") (pin "1") (pinfunction "GND_1") (pintype "bidirectional"))
      (node (ref "Z22") (pin "1") (pinfunction "GND_1") (pintype "bidirectional"))
      (node (ref "Z23") (pin "1") (pinfunction "GND_1") (pintype "bidirectional"))
      (node (ref "Z24") (pin "1") (pinfunction "GND_1") (pintype "bidirectional"))
      (node (ref "Z25") (pin "1") (pinfunction "GND_1") (pintype "bidirectional"))
      (node (ref "Z26") (pin "1") (pinfunction "GND_1") (pintype "bidirectional"))
      (node (ref "Z27") (pin "1") (pinfunction "GND_1") (pintype "bidirectional"))
      (node (ref "Z28") (pin "1") (pinfunction "GND_1") (pintype "bidirectional"))
      (node (ref "Z3") (pin "1") (pinfunction "GND_1") (pintype "bidirectional"))
      (node (ref "Z4") (pin "1") (pinfunction "GND_1") (pintype "bidirectional"))
      (node (ref "Z5") (pin "1") (pinfunction "GND_1") (pintype "bidirectional"))
      (node (ref "Z6") (pin "1") (pinfunction "GND_1") (pintype "bidirectional"))
      (node (ref "Z7") (pin "1") (pinfunction "GND_1") (pintype "bidirectional"))
      (node (ref "Z8") (pin "1") (pinfunction "GND_1") (pintype "bidirectional"))
      (node (ref "Z9") (pin "1") (pinfunction "GND_1") (pintype "bidirectional"))
    )
    (net (code "78") (name "GPS_EN") (class "Default")
      (node (ref "J8") (pin "39") (pinfunction "39_39") (pintype "passive"))
      (node (ref "J9") (pin "08") (pinfunction "08_08") (pintype "passive"))
    )
    (net (code "79") (name "GPS_RX") (class "Default")
      (node (ref "J8") (pin "37") (pinfunction "37_37") (pintype "passive"))
      (node (ref "J9") (pin "04") (pinfunction "04_04") (pintype "passive"))
    )
    (net (code "80") (name "GPS_TX") (class "Default")
      (node (ref "J8") (pin "35") (pinfunction "35_35") (pintype "passive"))
      (node (ref "J9") (pin "05") (pinfunction "05_05") (pintype "passive"))
    )
    (net (code "81") (name "IMU_DIN") (class "Default")
      (node (ref "J8") (pin "05") (pinfunction "05_05") (pintype "passive"))
    )
    (net (code "82") (name "IMU_DOUT") (class "Default")
      (node (ref "J8") (pin "07") (pinfunction "07_07") (pintype "passive"))
    )
    (net (code "83") (name "IMU_DR") (class "Default")
      (node (ref "J8") (pin "13") (pinfunction "13_13") (pintype "passive"))
    )
    (net (code "84") (name "IMU_SCLK") (class "Default")
      (node (ref "J8") (pin "09") (pinfunction "09_09") (pintype "passive"))
    )
    (net (code "85") (name "IMU_SYNC") (class "Default")
      (node (ref "J8") (pin "11") (pinfunction "11_11") (pintype "passive"))
    )
    (net (code "86") (name "IM_OUT1") (class "Default")
      (node (ref "Z15") (pin "4") (pinfunction "3_4") (pintype "bidirectional"))
    )
    (net (code "87") (name "IP_OUT1") (class "Default")
      (node (ref "Z15") (pin "5") (pinfunction "4_5") (pintype "bidirectional"))
    )
    (net (code "88") (name "ISO_MISO") (class "Default")
      (node (ref "J8") (pin "26") (pinfunction "26_26") (pintype "passive"))
    )
    (net (code "89") (name "ISO_MOSI") (class "Default")
      (node (ref "J8") (pin "24") (pinfunction "24_24") (pintype "passive"))
    )
    (net (code "90") (name "ISO_SPI_SCLK") (class "Default")
      (node (ref "J8") (pin "22") (pinfunction "22_22") (pintype "passive"))
    )
    (net (code "91") (name "ISO_SPI_SLOW") (class "Default")
      (node (ref "J8") (pin "30") (pinfunction "30_30") (pintype "passive"))
    )
    (net (code "92") (name "LED_OUT1") (class "Default")
      (node (ref "J7") (pin "22") (pinfunction "22_22") (pintype "passive"))
    )
    (net (code "93") (name "LED_OUT2") (class "Default")
      (node (ref "J7") (pin "20") (pinfunction "20_20") (pintype "passive"))
    )
    (net (code "94") (name "LED_OUT3") (class "Default")
      (node (ref "J7") (pin "18") (pinfunction "18_18") (pintype "passive"))
    )
    (net (code "95") (name "MASS_ON") (class "Default")
      (node (ref "J8") (pin "25") (pinfunction "25_25") (pintype "passive"))
    )
    (net (code "96") (name "MUX_0") (class "Default")
      (node (ref "J8") (pin "02") (pinfunction "02_02") (pintype "passive"))
    )
    (net (code "97") (name "MUX_1") (class "Default")
      (node (ref "J8") (pin "04") (pinfunction "04_04") (pintype "passive"))
    )
    (net (code "98") (name "MUX_2") (class "Default")
      (node (ref "J8") (pin "06") (pinfunction "06_06") (pintype "passive"))
    )
    (net (code "99") (name "MUX_3") (class "Default")
      (node (ref "J8") (pin "08") (pinfunction "08_08") (pintype "passive"))
    )
    (net (code "100") (name "NAND_SPI_CLK") (class "Default")
      (node (ref "J8") (pin "12") (pinfunction "12_12") (pintype "passive"))
    )
    (net (code "101") (name "NAND_SPI_SI{slash}IO0") (class "Default")
      (node (ref "J8") (pin "14") (pinfunction "14_14") (pintype "passive"))
    )
    (net (code "102") (name "NAND_SPI_SO{slash}IO1") (class "Default")
      (node (ref "J8") (pin "16") (pinfunction "16_16") (pintype "passive"))
    )
    (net (code "103") (name "NAND_SPI_~{HOLD{slash}IO03}") (class "Default")
      (node (ref "J8") (pin "20") (pinfunction "20_20") (pintype "passive"))
    )
    (net (code "104") (name "NAND_SPI_~{WP{slash}IO2}") (class "Default")
      (node (ref "J8") (pin "18") (pinfunction "18_18") (pintype "passive"))
    )
    (net (code "105") (name "OS0_ADC") (class "Default")
      (node (ref "J7") (pin "01") (pinfunction "01_01") (pintype "passive"))
    )
    (net (code "106") (name "OS1_ADC") (class "Default")
      (node (ref "J7") (pin "03") (pinfunction "03_03") (pintype "passive"))
    )
    (net (code "107") (name "OS2_ADC") (class "Default")
      (node (ref "J7") (pin "05") (pinfunction "05_05") (pintype "passive"))
    )
    (net (code "108") (name "PA0") (class "Default")
      (node (ref "J4") (pin "01") (pinfunction "01_01") (pintype "passive"))
      (node (ref "UC1") (pin "PA0") (pinfunction "PA0_PA0") (pintype "passive"))
    )
    (net (code "109") (name "PA3") (class "Default")
      (node (ref "J4") (pin "03") (pinfunction "03_03") (pintype "passive"))
      (node (ref "UC1") (pin "PA3") (pinfunction "PA3_PA3") (pintype "passive"))
    )
    (net (code "110") (name "PA4") (class "Default")
      (node (ref "J4") (pin "05") (pinfunction "05_05") (pintype "passive"))
      (node (ref "UC1") (pin "PA4") (pinfunction "PA4_PA4") (pintype "passive"))
    )
    (net (code "111") (name "PA5") (class "Default")
      (node (ref "J4") (pin "07") (pinfunction "07_07") (pintype "passive"))
      (node (ref "UC1") (pin "PA5") (pinfunction "PA5_PA5") (pintype "passive"))
    )
    (net (code "112") (name "PA6") (class "Default")
      (node (ref "J4") (pin "09") (pinfunction "09_09") (pintype "passive"))
      (node (ref "UC1") (pin "PA6") (pinfunction "PA6_PA6") (pintype "passive"))
    )
    (net (code "113") (name "PA8") (class "Default")
      (node (ref "J4") (pin "11") (pinfunction "11_11") (pintype "passive"))
      (node (ref "UC1") (pin "PA8") (pinfunction "PA8_PA8") (pintype "passive"))
    )
    (net (code "114") (name "PA9") (class "Default")
      (node (ref "J4") (pin "13") (pinfunction "13_13") (pintype "passive"))
      (node (ref "UC1") (pin "PA9") (pinfunction "PA9_PA9") (pintype "passive"))
    )
    (net (code "115") (name "PA10") (class "Default")
      (node (ref "J4") (pin "15") (pinfunction "15_15") (pintype "passive"))
      (node (ref "UC1") (pin "PA10") (pinfunction "PA10_PA10") (pintype "passive"))
    )
    (net (code "116") (name "PA11") (class "Default")
      (node (ref "J4") (pin "17") (pinfunction "17_17") (pintype "passive"))
      (node (ref "UC1") (pin "PA11") (pinfunction "PA11_PA11") (pintype "passive"))
    )
    (net (code "117") (name "PA12") (class "Default")
      (node (ref "J4") (pin "19") (pinfunction "19_19") (pintype "passive"))
      (node (ref "UC1") (pin "PA12") (pinfunction "PA12_PA12") (pintype "passive"))
    )
    (net (code "118") (name "PA13") (class "Default")
      (node (ref "J4") (pin "21") (pinfunction "21_21") (pintype "passive"))
      (node (ref "UC1") (pin "PA13") (pinfunction "PA13_PA13") (pintype "passive"))
    )
    (net (code "119") (name "PA14") (class "Default")
      (node (ref "J4") (pin "23") (pinfunction "23_23") (pintype "passive"))
      (node (ref "UC1") (pin "PA14") (pinfunction "PA14_PA14") (pintype "passive"))
    )
    (net (code "120") (name "PA15") (class "Default")
      (node (ref "J4") (pin "25") (pinfunction "25_25") (pintype "passive"))
      (node (ref "UC1") (pin "PA15") (pinfunction "PA15_PA15") (pintype "passive"))
    )
    (net (code "121") (name "PB0") (class "Default")
      (node (ref "J4") (pin "27") (pinfunction "27_27") (pintype "passive"))
      (node (ref "UC1") (pin "PB0") (pinfunction "PB0_PB0") (pintype "passive"))
    )
    (net (code "122") (name "PB1") (class "Default")
      (node (ref "J4") (pin "29") (pinfunction "29_29") (pintype "passive"))
      (node (ref "UC1") (pin "PB1") (pinfunction "PB1_PB1") (pintype "passive"))
    )
    (net (code "123") (name "PB2") (class "Default")
      (node (ref "J4") (pin "31") (pinfunction "31_31") (pintype "passive"))
      (node (ref "UC1") (pin "PB2") (pinfunction "PB2_PB2") (pintype "passive"))
    )
    (net (code "124") (name "PB3") (class "Default")
      (node (ref "J4") (pin "33") (pinfunction "33_33") (pintype "passive"))
      (node (ref "UC1") (pin "PB3") (pinfunction "PB3_PB3") (pintype "passive"))
    )
    (net (code "125") (name "PB4") (class "Default")
      (node (ref "J4") (pin "35") (pinfunction "35_35") (pintype "passive"))
      (node (ref "UC1") (pin "PB4") (pinfunction "PB4_PB4") (pintype "passive"))
    )
    (net (code "126") (name "PB5") (class "Default")
      (node (ref "J4") (pin "37") (pinfunction "37_37") (pintype "passive"))
      (node (ref "UC1") (pin "PB5") (pinfunction "PB5_PB5") (pintype "passive"))
    )
    (net (code "127") (name "PB6") (class "Default")
      (node (ref "J4") (pin "39") (pinfunction "39_39") (pintype "passive"))
      (node (ref "UC1") (pin "PB6") (pinfunction "PB6_PB6") (pintype "passive"))
    )
    (net (code "128") (name "PB7") (class "Default")
      (node (ref "J4") (pin "40") (pinfunction "40_40") (pintype "passive"))
      (node (ref "UC1") (pin "PB7") (pinfunction "PB7_PB7") (pintype "passive"))
    )
    (net (code "129") (name "PB8") (class "Default")
      (node (ref "J4") (pin "38") (pinfunction "38_38") (pintype "passive"))
      (node (ref "UC1") (pin "PB8") (pinfunction "PB8_PB8") (pintype "passive"))
    )
    (net (code "130") (name "PB9") (class "Default")
      (node (ref "J4") (pin "36") (pinfunction "36_36") (pintype "passive"))
      (node (ref "UC1") (pin "PB9") (pinfunction "PB9_PB9") (pintype "passive"))
    )
    (net (code "131") (name "PB10") (class "Default")
      (node (ref "J4") (pin "34") (pinfunction "34_34") (pintype "passive"))
      (node (ref "UC1") (pin "PB10") (pinfunction "PB10_PB10") (pintype "passive"))
    )
    (net (code "132") (name "PB11") (class "Default")
      (node (ref "J4") (pin "32") (pinfunction "32_32") (pintype "passive"))
      (node (ref "UC1") (pin "PB11") (pinfunction "PB11_PB11") (pintype "passive"))
    )
    (net (code "133") (name "PB12") (class "Default")
      (node (ref "J4") (pin "30") (pinfunction "30_30") (pintype "passive"))
      (node (ref "UC1") (pin "PB12") (pinfunction "PB12_PB12") (pintype "passive"))
    )
    (net (code "134") (name "PB13") (class "Default")
      (node (ref "J4") (pin "28") (pinfunction "28_28") (pintype "passive"))
    )
    (net (code "135") (name "PB14") (class "Default")
      (node (ref "J4") (pin "26") (pinfunction "26_26") (pintype "passive"))
      (node (ref "UC1") (pin "PB14") (pinfunction "PB14_PB14") (pintype "passive"))
    )
    (net (code "136") (name "PB15") (class "Default")
      (node (ref "J4") (pin "24") (pinfunction "24_24") (pintype "passive"))
      (node (ref "UC1") (pin "PB15") (pinfunction "PB15_PB15") (pintype "passive"))
    )
    (net (code "137") (name "PC0") (class "Default")
      (node (ref "J4") (pin "22") (pinfunction "22_22") (pintype "passive"))
      (node (ref "UC1") (pin "PC0") (pinfunction "PC0_PC0") (pintype "passive"))
    )
    (net (code "138") (name "PC2") (class "Default")
      (node (ref "J4") (pin "20") (pinfunction "20_20") (pintype "passive"))
      (node (ref "UC1") (pin "PC2") (pinfunction "PC2_PC2") (pintype "passive"))
    )
    (net (code "139") (name "PC3") (class "Default")
      (node (ref "J4") (pin "18") (pinfunction "18_18") (pintype "passive"))
      (node (ref "UC1") (pin "PC3") (pinfunction "PC3_PC3") (pintype "passive"))
    )
    (net (code "140") (name "PC6") (class "Default")
      (node (ref "J4") (pin "16") (pinfunction "16_16") (pintype "passive"))
      (node (ref "UC1") (pin "PC6") (pinfunction "PC6_PC6") (pintype "passive"))
    )
    (net (code "141") (name "PC7") (class "Default")
      (node (ref "J4") (pin "14") (pinfunction "14_14") (pintype "passive"))
      (node (ref "UC1") (pin "PC7") (pinfunction "PC7_PC7") (pintype "passive"))
    )
    (net (code "142") (name "PC8") (class "Default")
      (node (ref "J4") (pin "12") (pinfunction "12_12") (pintype "passive"))
      (node (ref "UC1") (pin "PC8") (pinfunction "PC8_PC8") (pintype "passive"))
    )
    (net (code "143") (name "PC9") (class "Default")
      (node (ref "J4") (pin "10") (pinfunction "10_10") (pintype "passive"))
      (node (ref "UC1") (pin "PC9") (pinfunction "PC9_PC9") (pintype "passive"))
    )
    (net (code "144") (name "PC10") (class "Default")
      (node (ref "J4") (pin "08") (pinfunction "08_08") (pintype "passive"))
      (node (ref "UC1") (pin "PC10") (pinfunction "PC10_PC10") (pintype "passive"))
    )
    (net (code "145") (name "PC11") (class "Default")
      (node (ref "J4") (pin "06") (pinfunction "06_06") (pintype "passive"))
      (node (ref "UC1") (pin "PC11") (pinfunction "PC11_PC11") (pintype "passive"))
    )
    (net (code "146") (name "PC12") (class "Default")
      (node (ref "J4") (pin "04") (pinfunction "04_04") (pintype "passive"))
      (node (ref "UC1") (pin "PC12") (pinfunction "PC12_PC12") (pintype "passive"))
    )
    (net (code "147") (name "PC13") (class "Default")
      (node (ref "J4") (pin "02") (pinfunction "02_02") (pintype "passive"))
      (node (ref "UC1") (pin "PC13") (pinfunction "PC13_PC13") (pintype "passive"))
    )
    (net (code "148") (name "PC14-0SC32_IN") (class "Default")
      (node (ref "UC1") (pin "PC14") (pinfunction "PC14_PC14") (pintype "passive"))
    )
    (net (code "149") (name "PC15-OSC32_OUT") (class "Default")
      (node (ref "UC1") (pin "PC15") (pinfunction "PC15_PC15") (pintype "passive"))
    )
    (net (code "150") (name "PD0") (class "Default")
      (node (ref "J5") (pin "01") (pinfunction "01_01") (pintype "passive"))
      (node (ref "UC1") (pin "PD0") (pinfunction "PD0_PD0") (pintype "passive"))
    )
    (net (code "151") (name "PD1") (class "Default")
      (node (ref "J5") (pin "03") (pinfunction "03_03") (pintype "passive"))
      (node (ref "UC1") (pin "PD1") (pinfunction "PD1_PD1") (pintype "passive"))
    )
    (net (code "152") (name "PD2") (class "Default")
      (node (ref "J5") (pin "05") (pinfunction "05_05") (pintype "passive"))
      (node (ref "UC1") (pin "PD2") (pinfunction "PD2_PD2") (pintype "passive"))
    )
    (net (code "153") (name "PD3") (class "Default")
      (node (ref "J5") (pin "07") (pinfunction "07_07") (pintype "passive"))
      (node (ref "UC1") (pin "PD3") (pinfunction "PD3_PD3") (pintype "passive"))
    )
    (net (code "154") (name "PD4") (class "Default")
      (node (ref "J5") (pin "09") (pinfunction "09_09") (pintype "passive"))
      (node (ref "UC1") (pin "PD4") (pinfunction "PD4_PD4") (pintype "passive"))
    )
    (net (code "155") (name "PD5") (class "Default")
      (node (ref "J5") (pin "11") (pinfunction "11_11") (pintype "passive"))
      (node (ref "UC1") (pin "PD5") (pinfunction "PD5_PD5") (pintype "passive"))
    )
    (net (code "156") (name "PD6") (class "Default")
      (node (ref "J5") (pin "13") (pinfunction "13_13") (pintype "passive"))
      (node (ref "UC1") (pin "PD6") (pinfunction "PD6_PD6") (pintype "passive"))
    )
    (net (code "157") (name "PD7") (class "Default")
      (node (ref "J5") (pin "15") (pinfunction "15_15") (pintype "passive"))
      (node (ref "UC1") (pin "PD7") (pinfunction "PD7_PD7") (pintype "passive"))
    )
    (net (code "158") (name "PD11") (class "Default")
      (node (ref "J5") (pin "17") (pinfunction "17_17") (pintype "passive"))
      (node (ref "UC1") (pin "PD11") (pinfunction "PD11_PD11") (pintype "passive"))
    )
    (net (code "159") (name "PD12") (class "Default")
      (node (ref "J5") (pin "19") (pinfunction "19_19") (pintype "passive"))
      (node (ref "UC1") (pin "PD12") (pinfunction "PD12_PD12") (pintype "passive"))
    )
    (net (code "160") (name "PD13") (class "Default")
      (node (ref "J5") (pin "21") (pinfunction "21_21") (pintype "passive"))
      (node (ref "UC1") (pin "PD13") (pinfunction "PD13_PD13") (pintype "passive"))
    )
    (net (code "161") (name "PD14") (class "Default")
      (node (ref "J5") (pin "23") (pinfunction "23_23") (pintype "passive"))
      (node (ref "UC1") (pin "PD14") (pinfunction "PD14_PD14") (pintype "passive"))
    )
    (net (code "162") (name "PD15") (class "Default")
      (node (ref "J5") (pin "25") (pinfunction "25_25") (pintype "passive"))
      (node (ref "UC1") (pin "PD15") (pinfunction "PD15_PD15") (pintype "passive"))
    )
    (net (code "163") (name "PE0") (class "Default")
      (node (ref "J5") (pin "27") (pinfunction "27_27") (pintype "passive"))
      (node (ref "UC1") (pin "PE0") (pinfunction "PE0_PE0") (pintype "passive"))
    )
    (net (code "164") (name "PE1") (class "Default")
      (node (ref "J5") (pin "29") (pinfunction "29_29") (pintype "passive"))
      (node (ref "UC1") (pin "PE1") (pinfunction "PE1_PE1") (pintype "passive"))
    )
    (net (code "165") (name "PE2") (class "Default")
      (node (ref "J5") (pin "31") (pinfunction "31_31") (pintype "passive"))
      (node (ref "UC1") (pin "PE2") (pinfunction "PE2_PE2") (pintype "passive"))
    )
    (net (code "166") (name "PE3") (class "Default")
      (node (ref "J5") (pin "33") (pinfunction "33_33") (pintype "passive"))
      (node (ref "UC1") (pin "PE3") (pinfunction "PE3_PE3") (pintype "passive"))
    )
    (net (code "167") (name "PE4") (class "Default")
      (node (ref "J5") (pin "35") (pinfunction "35_35") (pintype "passive"))
      (node (ref "UC1") (pin "PE4") (pinfunction "PE4_PE4") (pintype "passive"))
    )
    (net (code "168") (name "PE5") (class "Default")
      (node (ref "J5") (pin "37") (pinfunction "37_37") (pintype "passive"))
      (node (ref "UC1") (pin "PE5") (pinfunction "PE5_PE5") (pintype "passive"))
    )
    (net (code "169") (name "PE6") (class "Default")
      (node (ref "J5") (pin "39") (pinfunction "39_39") (pintype "passive"))
      (node (ref "UC1") (pin "PE6") (pinfunction "PE6_PE6") (pintype "passive"))
    )
    (net (code "170") (name "PE7") (class "Default")
      (node (ref "J5") (pin "40") (pinfunction "40_40") (pintype "passive"))
      (node (ref "UC1") (pin "PE7") (pinfunction "PE7_PE7") (pintype "passive"))
    )
    (net (code "171") (name "PE8") (class "Default")
      (node (ref "J5") (pin "38") (pinfunction "38_38") (pintype "passive"))
      (node (ref "UC1") (pin "PE8") (pinfunction "PE8_PE8") (pintype "passive"))
    )
    (net (code "172") (name "PE9") (class "Default")
      (node (ref "J5") (pin "36") (pinfunction "36_36") (pintype "passive"))
      (node (ref "UC1") (pin "PE9") (pinfunction "PE9_PE9") (pintype "passive"))
    )
    (net (code "173") (name "PE10") (class "Default")
      (node (ref "J5") (pin "34") (pinfunction "34_34") (pintype "passive"))
      (node (ref "UC1") (pin "PE10") (pinfunction "PE10_PE10") (pintype "passive"))
    )
    (net (code "174") (name "PE11") (class "Default")
      (node (ref "J5") (pin "32") (pinfunction "32_32") (pintype "passive"))
      (node (ref "UC1") (pin "PE11") (pinfunction "PE11_PE11") (pintype "passive"))
    )
    (net (code "175") (name "PE12") (class "Default")
      (node (ref "J5") (pin "30") (pinfunction "30_30") (pintype "passive"))
      (node (ref "UC1") (pin "PE12") (pinfunction "PE12_PE12") (pintype "passive"))
    )
    (net (code "176") (name "PE13") (class "Default")
      (node (ref "J5") (pin "28") (pinfunction "28_28") (pintype "passive"))
      (node (ref "UC1") (pin "PE13") (pinfunction "PE13_PE13") (pintype "passive"))
    )
    (net (code "177") (name "PE14") (class "Default")
      (node (ref "J5") (pin "26") (pinfunction "26_26") (pintype "passive"))
      (node (ref "UC1") (pin "PE14") (pinfunction "PE14_PE14") (pintype "passive"))
    )
    (net (code "178") (name "PE15") (class "Default")
      (node (ref "J5") (pin "24") (pinfunction "24_24") (pintype "passive"))
      (node (ref "UC1") (pin "PE15") (pinfunction "PE15_PE15") (pintype "passive"))
    )
    (net (code "179") (name "PF0") (class "Default")
      (node (ref "UC1") (pin "PF0") (pinfunction "PF0_PF0") (pintype "passive"))
    )
    (net (code "180") (name "PF1") (class "Default")
      (node (ref "J5") (pin "22") (pinfunction "22_22") (pintype "passive"))
      (node (ref "UC1") (pin "PF1") (pinfunction "PF1_PF1") (pintype "passive"))
    )
    (net (code "181") (name "PF2") (class "Default")
      (node (ref "J5") (pin "20") (pinfunction "20_20") (pintype "passive"))
      (node (ref "UC1") (pin "PF2") (pinfunction "PF2_PF2") (pintype "passive"))
    )
    (net (code "182") (name "PF3") (class "Default")
      (node (ref "J5") (pin "18") (pinfunction "18_18") (pintype "passive"))
      (node (ref "UC1") (pin "PF3") (pinfunction "PF3_PF3") (pintype "passive"))
    )
    (net (code "183") (name "PF4") (class "Default")
      (node (ref "J5") (pin "16") (pinfunction "16_16") (pintype "passive"))
      (node (ref "UC1") (pin "PF4") (pinfunction "PF4_PF4") (pintype "passive"))
    )
    (net (code "184") (name "PF5") (class "Default")
      (node (ref "J5") (pin "14") (pinfunction "14_14") (pintype "passive"))
      (node (ref "UC1") (pin "PF5") (pinfunction "PF5_PF5") (pintype "passive"))
    )
    (net (code "185") (name "PF6") (class "Default")
      (node (ref "J5") (pin "12") (pinfunction "12_12") (pintype "passive"))
      (node (ref "UC1") (pin "PF6") (pinfunction "PF6_PF6") (pintype "passive"))
    )
    (net (code "186") (name "PF7") (class "Default")
      (node (ref "J5") (pin "10") (pinfunction "10_10") (pintype "passive"))
      (node (ref "UC1") (pin "PF7") (pinfunction "PF7_PF7") (pintype "passive"))
    )
    (net (code "187") (name "PF8") (class "Default")
      (node (ref "J5") (pin "08") (pinfunction "08_08") (pintype "passive"))
      (node (ref "UC1") (pin "PF8") (pinfunction "PF8_PF8") (pintype "passive"))
    )
    (net (code "188") (name "PF9") (class "Default")
      (node (ref "J5") (pin "06") (pinfunction "06_06") (pintype "passive"))
      (node (ref "UC1") (pin "PF9") (pinfunction "PF9_PF9") (pintype "passive"))
    )
    (net (code "189") (name "PF10") (class "Default")
      (node (ref "J5") (pin "04") (pinfunction "04_04") (pintype "passive"))
      (node (ref "UC1") (pin "PF10") (pinfunction "PF10_PF10") (pintype "passive"))
    )
    (net (code "190") (name "PF11") (class "Default")
      (node (ref "J5") (pin "02") (pinfunction "02_02") (pintype "passive"))
      (node (ref "UC1") (pin "PF11") (pinfunction "PF11_PF11") (pintype "passive"))
    )
    (net (code "191") (name "PF12") (class "Default")
      (node (ref "J6") (pin "01") (pinfunction "01_01") (pintype "passive"))
      (node (ref "UC1") (pin "PF12") (pinfunction "PF12_PF12") (pintype "passive"))
    )
    (net (code "192") (name "PF13") (class "Default")
      (node (ref "J6") (pin "03") (pinfunction "03_03") (pintype "passive"))
      (node (ref "UC1") (pin "PF13") (pinfunction "PF13_PF13") (pintype "passive"))
    )
    (net (code "193") (name "PF14") (class "Default")
      (node (ref "J6") (pin "05") (pinfunction "05_05") (pintype "passive"))
      (node (ref "UC1") (pin "PF14") (pinfunction "PF14_PF14") (pintype "passive"))
    )
    (net (code "194") (name "PF15") (class "Default")
      (node (ref "J6") (pin "07") (pinfunction "07_07") (pintype "passive"))
      (node (ref "UC1") (pin "PF15") (pinfunction "PF15_PF15") (pintype "passive"))
    )
    (net (code "195") (name "PG0") (class "Default")
      (node (ref "J6") (pin "09") (pinfunction "09_09") (pintype "passive"))
      (node (ref "UC1") (pin "PG0") (pinfunction "PG0_PG0") (pintype "passive"))
    )
    (net (code "196") (name "PG1") (class "Default")
      (node (ref "J6") (pin "11") (pinfunction "11_11") (pintype "passive"))
      (node (ref "UC1") (pin "PG1") (pinfunction "PG1_PG1") (pintype "passive"))
    )
    (net (code "197") (name "PG2") (class "Default")
      (node (ref "J6") (pin "13") (pinfunction "13_13") (pintype "passive"))
      (node (ref "UC1") (pin "PG2") (pinfunction "PG2_PG2") (pintype "passive"))
    )
    (net (code "198") (name "PG3") (class "Default")
      (node (ref "J6") (pin "15") (pinfunction "15_15") (pintype "passive"))
      (node (ref "UC1") (pin "PG3") (pinfunction "PG3_PG3") (pintype "passive"))
    )
    (net (code "199") (name "PG4") (class "Default")
      (node (ref "J6") (pin "17") (pinfunction "17_17") (pintype "passive"))
      (node (ref "UC1") (pin "PG4") (pinfunction "PG4_PG4") (pintype "passive"))
    )
    (net (code "200") (name "PG5") (class "Default")
      (node (ref "J6") (pin "19") (pinfunction "19_19") (pintype "passive"))
      (node (ref "UC1") (pin "PG5") (pinfunction "PG5_PG5") (pintype "passive"))
    )
    (net (code "201") (name "PG6") (class "Default")
      (node (ref "J6") (pin "21") (pinfunction "21_21") (pintype "passive"))
      (node (ref "UC1") (pin "PG6") (pinfunction "PG6_PG6") (pintype "passive"))
    )
    (net (code "202") (name "PG7") (class "Default")
      (node (ref "J6") (pin "23") (pinfunction "23_23") (pintype "passive"))
    )
    (net (code "203") (name "PG8") (class "Default")
      (node (ref "J6") (pin "25") (pinfunction "25_25") (pintype "passive"))
      (node (ref "UC1") (pin "PG8") (pinfunction "PG8_PG8") (pintype "passive"))
    )
    (net (code "204") (name "PG9") (class "Default")
      (node (ref "J6") (pin "27") (pinfunction "27_27") (pintype "passive"))
      (node (ref "UC1") (pin "PG9") (pinfunction "PG9_PG9") (pintype "passive"))
    )
    (net (code "205") (name "PG10") (class "Default")
      (node (ref "J6") (pin "29") (pinfunction "29_29") (pintype "passive"))
      (node (ref "UC1") (pin "PG10") (pinfunction "PG10_PG10") (pintype "passive"))
    )
    (net (code "206") (name "PG12") (class "Default")
      (node (ref "J6") (pin "31") (pinfunction "31_31") (pintype "passive"))
      (node (ref "UC1") (pin "PG12") (pinfunction "PG12_PG12") (pintype "passive"))
    )
    (net (code "207") (name "PG14") (class "Default")
      (node (ref "J6") (pin "33") (pinfunction "33_33") (pintype "passive"))
      (node (ref "UC1") (pin "PG14") (pinfunction "PG14_PG14") (pintype "passive"))
    )
    (net (code "208") (name "PG15") (class "Default")
      (node (ref "J6") (pin "35") (pinfunction "35_35") (pintype "passive"))
      (node (ref "UC1") (pin "PG15") (pinfunction "PG15_PG15") (pintype "passive"))
    )
    (net (code "209") (name "PH0-OSC_IN") (class "Default")
      (node (ref "UC1") (pin "PH0") (pinfunction "PH0_PH0") (pintype "passive"))
    )
    (net (code "210") (name "PH1") (class "Default")
      (node (ref "J6") (pin "37") (pinfunction "37_37") (pintype "passive"))
      (node (ref "UC1") (pin "PH1") (pinfunction "PH1_PH1") (pintype "passive"))
    )
    (net (code "211") (name "POWER_FAULT1") (class "Default")
      (node (ref "J2") (pin "7") (pinfunction "7_7") (pintype "passive"))
      (node (ref "J8") (pin "15") (pinfunction "15_15") (pintype "passive"))
    )
    (net (code "212") (name "POWER_FAULT2") (class "Default")
      (node (ref "J2") (pin "9") (pinfunction "9_9") (pintype "passive"))
      (node (ref "J8") (pin "17") (pinfunction "17_17") (pintype "passive"))
    )
    (net (code "213") (name "POWER_FAULT3") (class "Default")
      (node (ref "J2") (pin "11") (pinfunction "11_11") (pintype "passive"))
      (node (ref "J8") (pin "19") (pinfunction "19_19") (pintype "passive"))
    )
    (net (code "214") (name "PPS_NC") (class "Default")
      (node (ref "J9") (pin "01") (pinfunction "01_01") (pintype "passive"))
    )
    (net (code "215") (name "P_LED") (class "Default")
      (node (ref "J7") (pin "24") (pinfunction "24_24") (pintype "passive"))
    )
    (net (code "216") (name "RESET_ADC") (class "Default")
      (node (ref "J7") (pin "09") (pinfunction "09_09") (pintype "passive"))
    )
    (net (code "217") (name "SCL1") (class "Default")
      (node (ref "J8") (pin "23") (pinfunction "23_23") (pintype "passive"))
    )
    (net (code "218") (name "SCL2") (class "Default")
      (node (ref "J8") (pin "29") (pinfunction "29_29") (pintype "passive"))
    )
    (net (code "219") (name "SCLK_ADC") (class "Default")
      (node (ref "J7") (pin "11") (pinfunction "11_11") (pintype "passive"))
    )
    (net (code "220") (name "SDA1") (class "Default")
      (node (ref "J8") (pin "21") (pinfunction "21_21") (pintype "passive"))
    )
    (net (code "221") (name "SDA2") (class "Default")
      (node (ref "J8") (pin "27") (pinfunction "27_27") (pintype "passive"))
    )
    (net (code "222") (name "SOURCE1_") (class "Default")
      (node (ref "Z1") (pin "2") (pinfunction "1_2") (pintype "bidirectional"))
    )
    (net (code "223") (name "SOURCE1_0") (class "Default")
      (node (ref "Z3") (pin "2") (pinfunction "1_2") (pintype "bidirectional"))
    )
    (net (code "224") (name "SOURCE1_1") (class "Default")
      (node (ref "Z21") (pin "2") (pinfunction "1_2") (pintype "bidirectional"))
    )
    (net (code "225") (name "SOURCE1_2") (class "Default")
      (node (ref "Z23") (pin "2") (pinfunction "1_2") (pintype "bidirectional"))
    )
    (net (code "226") (name "SOURCE1_3") (class "Default")
      (node (ref "Z5") (pin "2") (pinfunction "1_2") (pintype "bidirectional"))
    )
    (net (code "227") (name "SOURCE1_4") (class "Default")
      (node (ref "Z7") (pin "2") (pinfunction "1_2") (pintype "bidirectional"))
    )
    (net (code "228") (name "SOURCE1_5") (class "Default")
      (node (ref "Z17") (pin "2") (pinfunction "1_2") (pintype "bidirectional"))
    )
    (net (code "229") (name "SOURCE1_6") (class "Default")
      (node (ref "Z19") (pin "2") (pinfunction "1_2") (pintype "bidirectional"))
    )
    (net (code "230") (name "SOURCE1_7") (class "Default")
      (node (ref "Z9") (pin "2") (pinfunction "1_2") (pintype "bidirectional"))
    )
    (net (code "231") (name "SOURCE1_8") (class "Default")
      (node (ref "Z11") (pin "2") (pinfunction "1_2") (pintype "bidirectional"))
    )
    (net (code "232") (name "SOURCE1_9") (class "Default")
      (node (ref "Z13") (pin "2") (pinfunction "1_2") (pintype "bidirectional"))
    )
    (net (code "233") (name "SOURCE1_10") (class "Default")
      (node (ref "Z15") (pin "2") (pinfunction "1_2") (pintype "bidirectional"))
    )
    (net (code "234") (name "SOURCE1_11") (class "Default")
      (node (ref "Z25") (pin "2") (pinfunction "1_2") (pintype "bidirectional"))
      (node (ref "Z25") (pin "5") (pinfunction "4_5") (pintype "bidirectional"))
    )
    (net (code "235") (name "SOURCE1_12") (class "Default")
      (node (ref "Z27") (pin "2") (pinfunction "1_2") (pintype "bidirectional"))
      (node (ref "Z27") (pin "5") (pinfunction "4_5") (pintype "bidirectional"))
    )
    (net (code "236") (name "SOURCE2_") (class "Default")
      (node (ref "Z2") (pin "2") (pinfunction "1_2") (pintype "bidirectional"))
    )
    (net (code "237") (name "SOURCE2_0") (class "Default")
      (node (ref "Z4") (pin "2") (pinfunction "1_2") (pintype "bidirectional"))
    )
    (net (code "238") (name "SOURCE2_1") (class "Default")
      (node (ref "Z22") (pin "2") (pinfunction "1_2") (pintype "bidirectional"))
    )
    (net (code "239") (name "SOURCE2_2") (class "Default")
      (node (ref "Z24") (pin "2") (pinfunction "1_2") (pintype "bidirectional"))
    )
    (net (code "240") (name "SOURCE2_3") (class "Default")
      (node (ref "Z6") (pin "2") (pinfunction "1_2") (pintype "bidirectional"))
    )
    (net (code "241") (name "SOURCE2_4") (class "Default")
      (node (ref "Z8") (pin "2") (pinfunction "1_2") (pintype "bidirectional"))
    )
    (net (code "242") (name "SOURCE2_5") (class "Default")
      (node (ref "Z18") (pin "2") (pinfunction "1_2") (pintype "bidirectional"))
    )
    (net (code "243") (name "SOURCE2_6") (class "Default")
      (node (ref "Z20") (pin "2") (pinfunction "1_2") (pintype "bidirectional"))
    )
    (net (code "244") (name "SOURCE2_7") (class "Default")
      (node (ref "Z10") (pin "2") (pinfunction "1_2") (pintype "bidirectional"))
    )
    (net (code "245") (name "SOURCE2_8") (class "Default")
      (node (ref "Z12") (pin "2") (pinfunction "1_2") (pintype "bidirectional"))
    )
    (net (code "246") (name "SOURCE2_9") (class "Default")
      (node (ref "Z14") (pin "2") (pinfunction "1_2") (pintype "bidirectional"))
    )
    (net (code "247") (name "SOURCE2_10") (class "Default")
      (node (ref "Z16") (pin "2") (pinfunction "1_2") (pintype "bidirectional"))
    )
    (net (code "248") (name "SOURCE2_11") (class "Default")
      (node (ref "Z26") (pin "2") (pinfunction "1_2") (pintype "bidirectional"))
      (node (ref "Z26") (pin "5") (pinfunction "4_5") (pintype "bidirectional"))
    )
    (net (code "249") (name "SOURCE2_12") (class "Default")
      (node (ref "Z28") (pin "2") (pinfunction "1_2") (pintype "bidirectional"))
      (node (ref "Z28") (pin "5") (pinfunction "4_5") (pintype "bidirectional"))
    )
    (net (code "250") (name "THERMOCOUPLE_MISO") (class "Default")
      (node (ref "J8") (pin "34") (pinfunction "34_34") (pintype "passive"))
    )
    (net (code "251") (name "THERMOCOUPLE_SCLK") (class "Default")
      (node (ref "J8") (pin "32") (pinfunction "32_32") (pintype "passive"))
    )
    (net (code "252") (name "USART3_TX") (class "Default")
      (node (ref "UC1") (pin "PD8") (pinfunction "PD8_PD8") (pintype "passive"))
    )
    (net (code "253") (name "USART4_RX") (class "Default")
      (node (ref "UC1") (pin "PD9") (pinfunction "PD9_PD9") (pintype "passive"))
    )
    (net (code "254") (name "USB_FS_OVCR") (class "Default")
      (node (ref "UC1") (pin "PG7") (pinfunction "PG7_PG7") (pintype "passive"))
    )
    (net (code "255") (name "USB_FS_PWR_EN") (class "Default")
      (node (ref "UC1") (pin "PD10") (pinfunction "PD10_PD10") (pintype "passive"))
    )
    (net (code "256") (name "VBAT_NC") (class "Default")
      (node (ref "J9") (pin "07") (pinfunction "07_07") (pintype "passive"))
    )
    (net (code "257") (name "unconnected-(J1-Pad2)") (class "Default")
      (node (ref "J1") (pin "2") (pinfunction "2_2") (pintype "passive"))
    )
    (net (code "258") (name "unconnected-(J1-Pad4)") (class "Default")
      (node (ref "J1") (pin "4") (pinfunction "4_4") (pintype "passive"))
    )
    (net (code "259") (name "unconnected-(J1-Pad6)") (class "Default")
      (node (ref "J1") (pin "6") (pinfunction "6_6") (pintype "passive"))
    )
    (net (code "260") (name "unconnected-(J1-Pad8)") (class "Default")
      (node (ref "J1") (pin "8") (pinfunction "8_8") (pintype "passive"))
    )
    (net (code "261") (name "unconnected-(J7-Pad02)") (class "Default")
      (node (ref "J7") (pin "02") (pinfunction "02_02") (pintype "passive"))
    )
    (net (code "262") (name "unconnected-(J7-Pad04)") (class "Default")
      (node (ref "J7") (pin "04") (pinfunction "04_04") (pintype "passive"))
    )
    (net (code "263") (name "unconnected-(J7-Pad06)") (class "Default")
      (node (ref "J7") (pin "06") (pinfunction "06_06") (pintype "passive"))
    )
    (net (code "264") (name "unconnected-(J7-Pad08)") (class "Default")
      (node (ref "J7") (pin "08") (pinfunction "08_08") (pintype "passive"))
    )
    (net (code "265") (name "unconnected-(J7-Pad10)") (class "Default")
      (node (ref "J7") (pin "10") (pinfunction "10_10") (pintype "passive"))
    )
    (net (code "266") (name "unconnected-(J7-Pad12)") (class "Default")
      (node (ref "J7") (pin "12") (pinfunction "12_12") (pintype "passive"))
    )
    (net (code "267") (name "unconnected-(J7-Pad14)") (class "Default")
      (node (ref "J7") (pin "14") (pinfunction "14_14") (pintype "passive"))
    )
    (net (code "268") (name "unconnected-(J7-Pad16)") (class "Default")
      (node (ref "J7") (pin "16") (pinfunction "16_16") (pintype "passive"))
    )
    (net (code "269") (name "unconnected-(J7-Pad39)") (class "Default")
      (node (ref "J7") (pin "39") (pinfunction "39_39") (pintype "passive"))
    )
    (net (code "270") (name "unconnected-(J8-Pad31)") (class "Default")
      (node (ref "J8") (pin "31") (pinfunction "31_31") (pintype "passive"))
    )
    (net (code "271") (name "unconnected-(J8-Pad33)") (class "Default")
      (node (ref "J8") (pin "33") (pinfunction "33_33") (pintype "passive"))
    )
    (net (code "272") (name "unconnected-(J8-Pad38)") (class "Default")
      (node (ref "J8") (pin "38") (pinfunction "38_38") (pintype "passive"))
    )
    (net (code "273") (name "unconnected-(J8-Pad40)") (class "Default")
      (node (ref "J8") (pin "40") (pinfunction "40_40") (pintype "passive"))
    )
    (net (code "274") (name "unconnected-(UC1-AGND-Pad31_AGND)") (class "Default")
      (node (ref "UC1") (pin "31_AGND") (pinfunction "AGND_31_AGND") (pintype "passive"))
    )
    (net (code "275") (name "unconnected-(UC1-Pad3V3)") (class "Default")
      (node (ref "UC1") (pin "3V3") (pinfunction "3V3_3V3") (pintype "passive"))
    )
    (net (code "276") (name "unconnected-(UC1-Pad5V)") (class "Default")
      (node (ref "UC1") (pin "5V") (pinfunction "5V_5V") (pintype "passive"))
    )
    (net (code "277") (name "unconnected-(UC1-Pad5V_USB_STLK)") (class "Default")
      (node (ref "UC1") (pin "5V_USB_STLK") (pinfunction "5V_USB_STLK_5V_USB_STLK") (pintype "passive"))
    )
    (net (code "278") (name "unconnected-(UC1-PadBOOT0)") (class "Default")
      (node (ref "UC1") (pin "BOOT0") (pinfunction "BOOT0_BOOT0") (pintype "passive"))
    )
    (net (code "279") (name "unconnected-(UC1-PadIOREF)") (class "Default")
      (node (ref "UC1") (pin "IOREF") (pinfunction "IOREF_IOREF") (pintype "passive"))
    )
    (net (code "280") (name "unconnected-(UC1-PadNC_1)") (class "Default")
      (node (ref "UC1") (pin "NC_1") (pinfunction "NC_1_NC_1") (pintype "passive"))
    )
    (net (code "281") (name "unconnected-(UC1-PadNC_2)") (class "Default")
      (node (ref "UC1") (pin "NC_2") (pinfunction "NC_2_NC_2") (pintype "passive"))
    )
    (net (code "282") (name "unconnected-(UC1-PadNC_3)") (class "Default")
      (node (ref "UC1") (pin "NC_3") (pinfunction "NC_3_NC_3") (pintype "passive"))
    )
    (net (code "283") (name "unconnected-(UC1-PadNRST)") (class "Default")
      (node (ref "UC1") (pin "NRST") (pinfunction "NRST_NRST") (pintype "passive"))
    )
    (net (code "284") (name "unconnected-(UC1-PadVBAT)") (class "Default")
      (node (ref "UC1") (pin "VBAT") (pinfunction "VBAT_VBAT") (pintype "passive"))
    )
    (net (code "285") (name "unconnected-(UC1-PadVIN)") (class "Default")
      (node (ref "UC1") (pin "VIN") (pinfunction "VIN_VIN") (pintype "passive"))
    )
    (net (code "286") (name "unconnected-(UC1-PadVREFP)") (class "Default")
      (node (ref "UC1") (pin "VREFP") (pinfunction "VREFP_VREFP") (pintype "passive"))
    )
    (net (code "287") (name "unconnected-(Z1-2-Pad3)") (class "Default")
      (node (ref "Z1") (pin "3") (pinfunction "2_3") (pintype "bidirectional"))
    )
    (net (code "288") (name "unconnected-(Z1-3-Pad4)") (class "Default")
      (node (ref "Z1") (pin "4") (pinfunction "3_4") (pintype "bidirectional"))
    )
    (net (code "289") (name "unconnected-(Z2-2-Pad3)") (class "Default")
      (node (ref "Z2") (pin "3") (pinfunction "2_3") (pintype "bidirectional"))
    )
    (net (code "290") (name "unconnected-(Z2-3-Pad4)") (class "Default")
      (node (ref "Z2") (pin "4") (pinfunction "3_4") (pintype "bidirectional"))
    )
    (net (code "291") (name "unconnected-(Z3-2-Pad3)") (class "Default")
      (node (ref "Z3") (pin "3") (pinfunction "2_3") (pintype "bidirectional"))
    )
    (net (code "292") (name "unconnected-(Z3-3-Pad4)") (class "Default")
      (node (ref "Z3") (pin "4") (pinfunction "3_4") (pintype "bidirectional"))
    )
    (net (code "293") (name "unconnected-(Z4-2-Pad3)") (class "Default")
      (node (ref "Z4") (pin "3") (pinfunction "2_3") (pintype "bidirectional"))
    )
    (net (code "294") (name "unconnected-(Z4-3-Pad4)") (class "Default")
      (node (ref "Z4") (pin "4") (pinfunction "3_4") (pintype "bidirectional"))
    )
    (net (code "295") (name "unconnected-(Z5-2-Pad3)") (class "Default")
      (node (ref "Z5") (pin "3") (pinfunction "2_3") (pintype "bidirectional"))
    )
    (net (code "296") (name "unconnected-(Z5-3-Pad4)") (class "Default")
      (node (ref "Z5") (pin "4") (pinfunction "3_4") (pintype "bidirectional"))
    )
    (net (code "297") (name "unconnected-(Z6-2-Pad3)") (class "Default")
      (node (ref "Z6") (pin "3") (pinfunction "2_3") (pintype "bidirectional"))
    )
    (net (code "298") (name "unconnected-(Z6-3-Pad4)") (class "Default")
      (node (ref "Z6") (pin "4") (pinfunction "3_4") (pintype "bidirectional"))
    )
    (net (code "299") (name "unconnected-(Z7-2-Pad3)") (class "Default")
      (node (ref "Z7") (pin "3") (pinfunction "2_3") (pintype "bidirectional"))
    )
    (net (code "300") (name "unconnected-(Z7-3-Pad4)") (class "Default")
      (node (ref "Z7") (pin "4") (pinfunction "3_4") (pintype "bidirectional"))
    )
    (net (code "301") (name "unconnected-(Z8-2-Pad3)") (class "Default")
      (node (ref "Z8") (pin "3") (pinfunction "2_3") (pintype "bidirectional"))
    )
    (net (code "302") (name "unconnected-(Z8-3-Pad4)") (class "Default")
      (node (ref "Z8") (pin "4") (pinfunction "3_4") (pintype "bidirectional"))
    )
    (net (code "303") (name "unconnected-(Z9-2-Pad3)") (class "Default")
      (node (ref "Z9") (pin "3") (pinfunction "2_3") (pintype "bidirectional"))
    )
    (net (code "304") (name "unconnected-(Z9-3-Pad4)") (class "Default")
      (node (ref "Z9") (pin "4") (pinfunction "3_4") (pintype "bidirectional"))
    )
    (net (code "305") (name "unconnected-(Z10-2-Pad3)") (class "Default")
      (node (ref "Z10") (pin "3") (pinfunction "2_3") (pintype "bidirectional"))
    )
    (net (code "306") (name "unconnected-(Z10-3-Pad4)") (class "Default")
      (node (ref "Z10") (pin "4") (pinfunction "3_4") (pintype "bidirectional"))
    )
    (net (code "307") (name "unconnected-(Z11-2-Pad3)") (class "Default")
      (node (ref "Z11") (pin "3") (pinfunction "2_3") (pintype "bidirectional"))
    )
    (net (code "308") (name "unconnected-(Z11-3-Pad4)") (class "Default")
      (node (ref "Z11") (pin "4") (pinfunction "3_4") (pintype "bidirectional"))
    )
    (net (code "309") (name "unconnected-(Z12-2-Pad3)") (class "Default")
      (node (ref "Z12") (pin "3") (pinfunction "2_3") (pintype "bidirectional"))
    )
    (net (code "310") (name "unconnected-(Z12-3-Pad4)") (class "Default")
      (node (ref "Z12") (pin "4") (pinfunction "3_4") (pintype "bidirectional"))
    )
    (net (code "311") (name "unconnected-(Z13-2-Pad3)") (class "Default")
      (node (ref "Z13") (pin "3") (pinfunction "2_3") (pintype "bidirectional"))
    )
    (net (code "312") (name "unconnected-(Z13-3-Pad4)") (class "Default")
      (node (ref "Z13") (pin "4") (pinfunction "3_4") (pintype "bidirectional"))
    )
    (net (code "313") (name "unconnected-(Z17-2-Pad3)") (class "Default")
      (node (ref "Z17") (pin "3") (pinfunction "2_3") (pintype "bidirectional"))
    )
    (net (code "314") (name "unconnected-(Z17-3-Pad4)") (class "Default")
      (node (ref "Z17") (pin "4") (pinfunction "3_4") (pintype "bidirectional"))
    )
    (net (code "315") (name "unconnected-(Z18-2-Pad3)") (class "Default")
      (node (ref "Z18") (pin "3") (pinfunction "2_3") (pintype "bidirectional"))
    )
    (net (code "316") (name "unconnected-(Z18-3-Pad4)") (class "Default")
      (node (ref "Z18") (pin "4") (pinfunction "3_4") (pintype "bidirectional"))
    )
    (net (code "317") (name "unconnected-(Z19-2-Pad3)") (class "Default")
      (node (ref "Z19") (pin "3") (pinfunction "2_3") (pintype "bidirectional"))
    )
    (net (code "318") (name "unconnected-(Z19-3-Pad4)") (class "Default")
      (node (ref "Z19") (pin "4") (pinfunction "3_4") (pintype "bidirectional"))
    )
    (net (code "319") (name "unconnected-(Z20-2-Pad3)") (class "Default")
      (node (ref "Z20") (pin "3") (pinfunction "2_3") (pintype "bidirectional"))
    )
    (net (code "320") (name "unconnected-(Z20-3-Pad4)") (class "Default")
      (node (ref "Z20") (pin "4") (pinfunction "3_4") (pintype "bidirectional"))
    )
    (net (code "321") (name "unconnected-(Z21-2-Pad3)") (class "Default")
      (node (ref "Z21") (pin "3") (pinfunction "2_3") (pintype "bidirectional"))
    )
    (net (code "322") (name "unconnected-(Z21-3-Pad4)") (class "Default")
      (node (ref "Z21") (pin "4") (pinfunction "3_4") (pintype "bidirectional"))
    )
    (net (code "323") (name "unconnected-(Z22-2-Pad3)") (class "Default")
      (node (ref "Z22") (pin "3") (pinfunction "2_3") (pintype "bidirectional"))
    )
    (net (code "324") (name "unconnected-(Z22-3-Pad4)") (class "Default")
      (node (ref "Z22") (pin "4") (pinfunction "3_4") (pintype "bidirectional"))
    )
    (net (code "325") (name "unconnected-(Z23-2-Pad3)") (class "Default")
      (node (ref "Z23") (pin "3") (pinfunction "2_3") (pintype "bidirectional"))
    )
    (net (code "326") (name "unconnected-(Z23-3-Pad4)") (class "Default")
      (node (ref "Z23") (pin "4") (pinfunction "3_4") (pintype "bidirectional"))
    )
    (net (code "327") (name "unconnected-(Z24-2-Pad3)") (class "Default")
      (node (ref "Z24") (pin "3") (pinfunction "2_3") (pintype "bidirectional"))
    )
    (net (code "328") (name "unconnected-(Z24-3-Pad4)") (class "Default")
      (node (ref "Z24") (pin "4") (pinfunction "3_4") (pintype "bidirectional"))
    )
    (net (code "329") (name "unconnected-(Z25-2-Pad3)") (class "Default")
      (node (ref "Z25") (pin "3") (pinfunction "2_3") (pintype "bidirectional"))
    )
    (net (code "330") (name "unconnected-(Z25-3-Pad4)") (class "Default")
      (node (ref "Z25") (pin "4") (pinfunction "3_4") (pintype "bidirectional"))
    )
    (net (code "331") (name "unconnected-(Z26-2-Pad3)") (class "Default")
      (node (ref "Z26") (pin "3") (pinfunction "2_3") (pintype "bidirectional"))
    )
    (net (code "332") (name "unconnected-(Z26-3-Pad4)") (class "Default")
      (node (ref "Z26") (pin "4") (pinfunction "3_4") (pintype "bidirectional"))
    )
    (net (code "333") (name "unconnected-(Z27-2-Pad3)") (class "Default")
      (node (ref "Z27") (pin "3") (pinfunction "2_3") (pintype "bidirectional"))
    )
    (net (code "334") (name "unconnected-(Z27-3-Pad4)") (class "Default")
      (node (ref "Z27") (pin "4") (pinfunction "3_4") (pintype "bidirectional"))
    )
    (net (code "335") (name "~{CS_ADC}") (class "Default")
      (node (ref "J7") (pin "13") (pinfunction "13_13") (pintype "passive"))
    )
    (net (code "336") (name "~{CS_INPUT_NAND}") (class "Default")
      (node (ref "J8") (pin "10") (pinfunction "10_10") (pintype "passive"))
    )
    (net (code "337") (name "~{IMU_CS}") (class "Default")
      (node (ref "J8") (pin "03") (pinfunction "03_03") (pintype "passive"))
    )
    (net (code "338") (name "~{IMU_RST}") (class "Default")
      (node (ref "J8") (pin "01") (pinfunction "01_01") (pintype "passive"))
    )
    (net (code "339") (name "~{ISO_CS}") (class "Default")
      (node (ref "J8") (pin "28") (pinfunction "28_28") (pintype "passive"))
    )
    (net (code "340") (name "~{THERMOCOUPLE_CS}") (class "Default")
      (node (ref "J8") (pin "36") (pinfunction "36_36") (pintype "passive"))
    )
  )
)
